# SW.net
KiCad netlist of a schematic drawn in Altium Designer
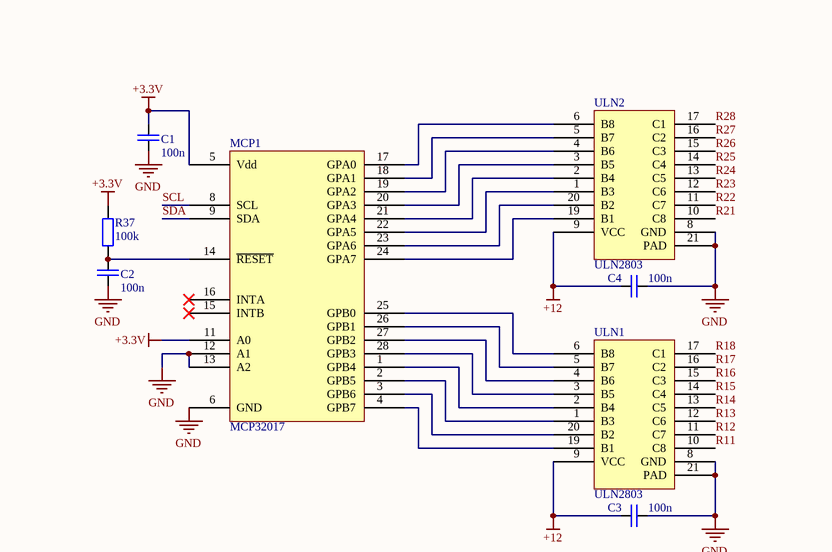
[diagram p0: SW.SchDoc, top left]
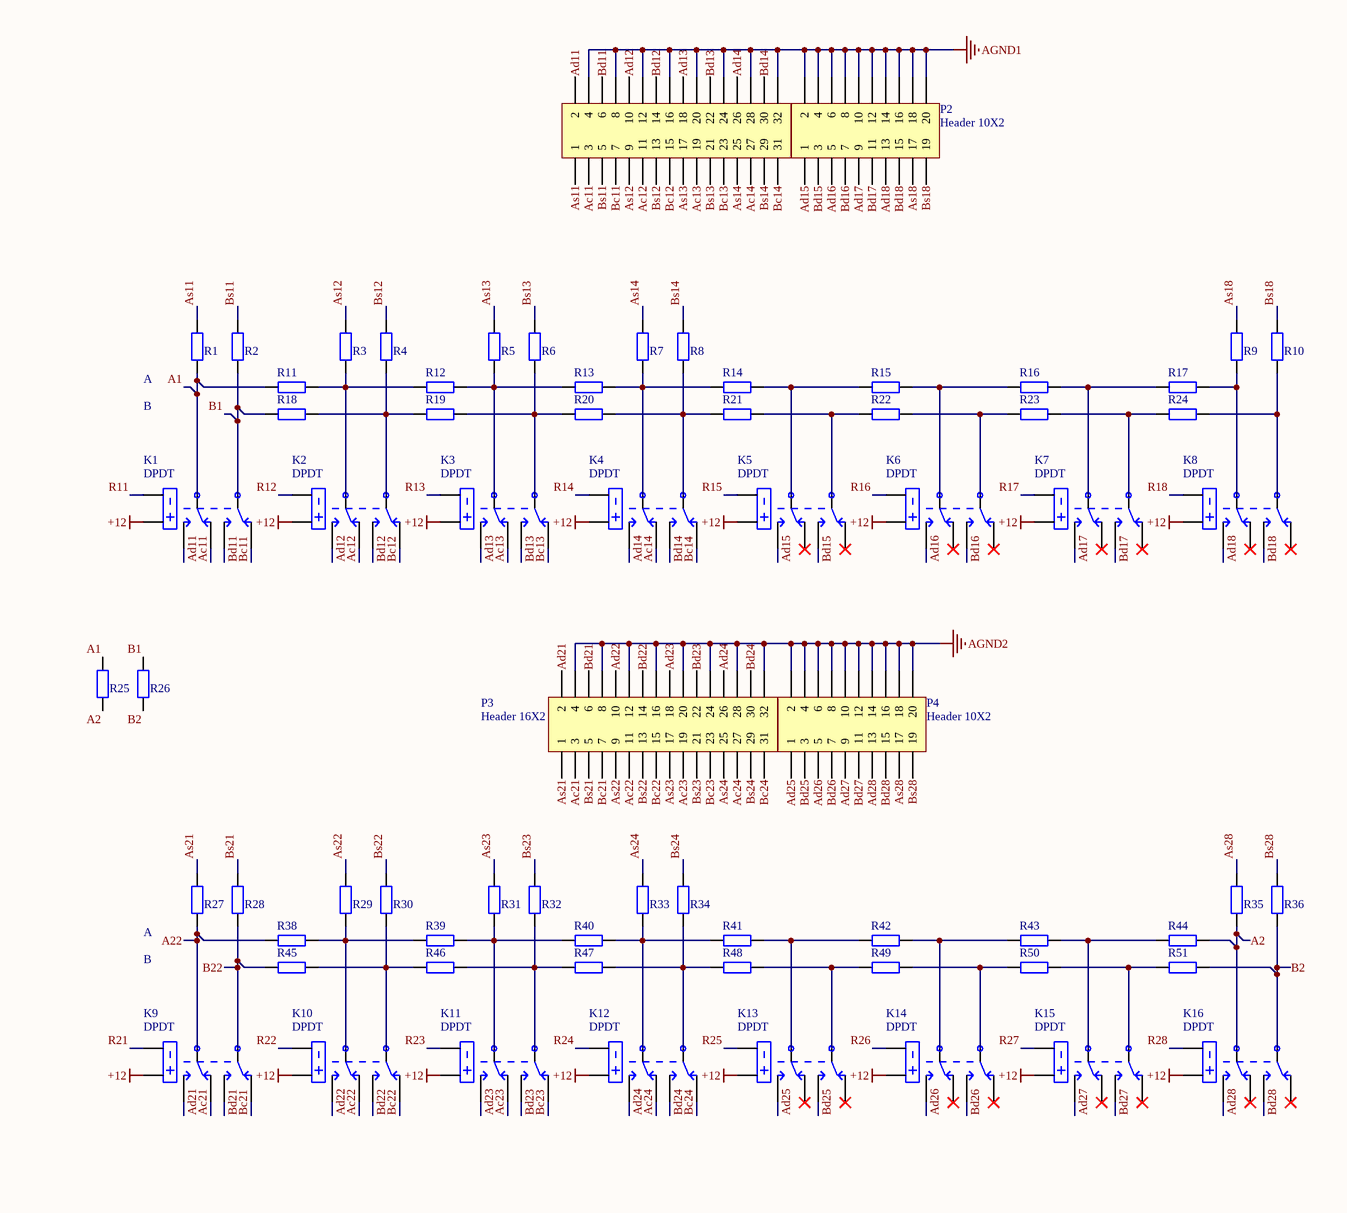
[diagram p1: SW.SchDoc, top right]
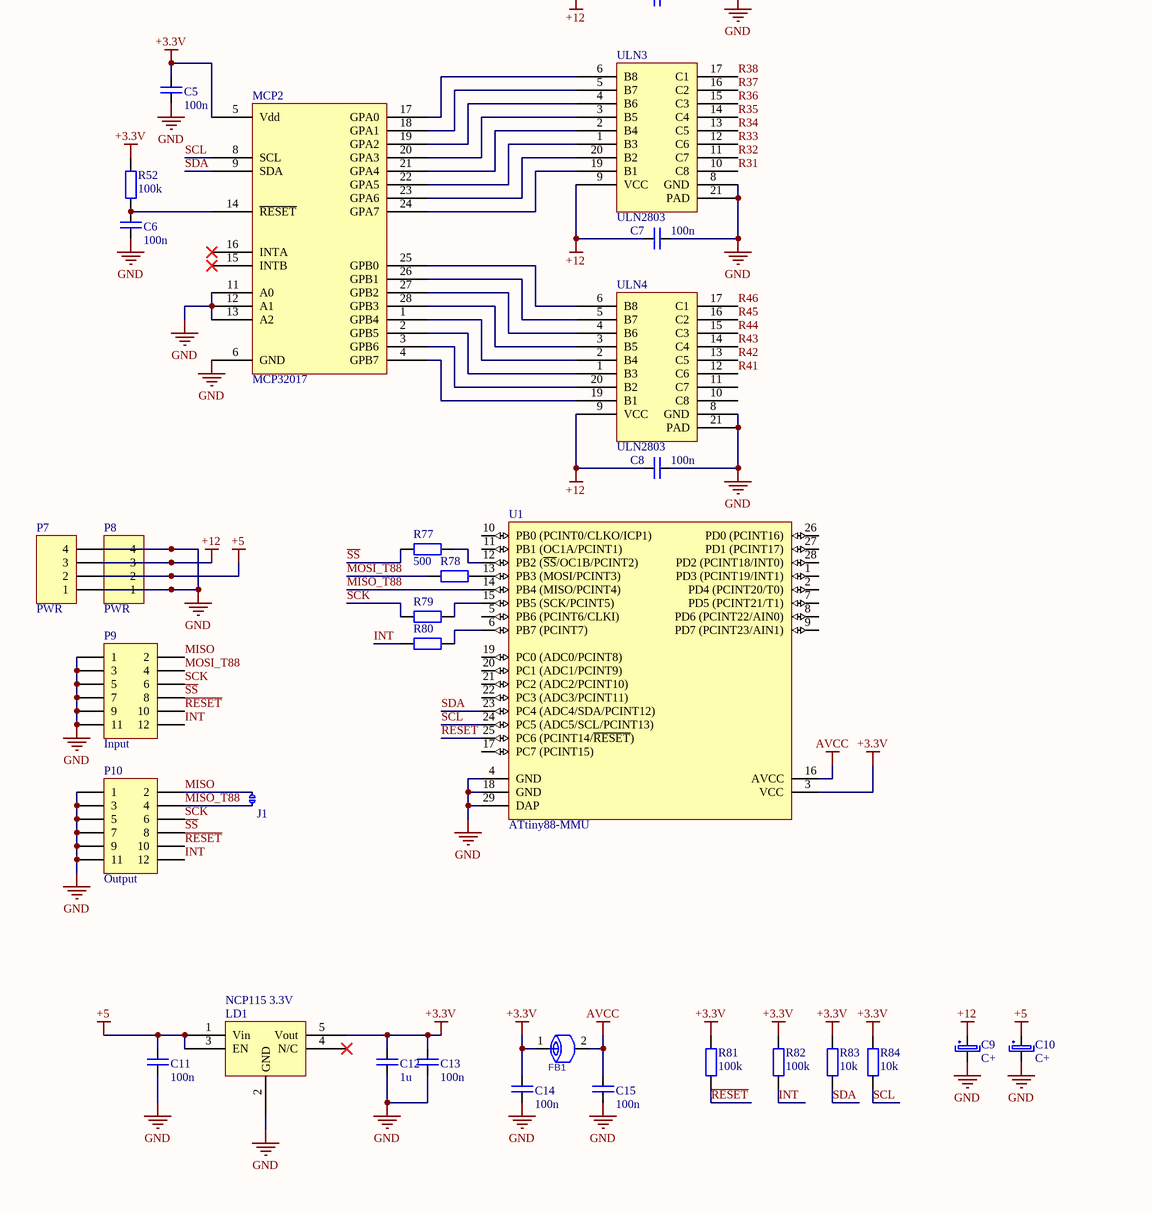
[diagram p2: SW.SchDoc, bottom left]
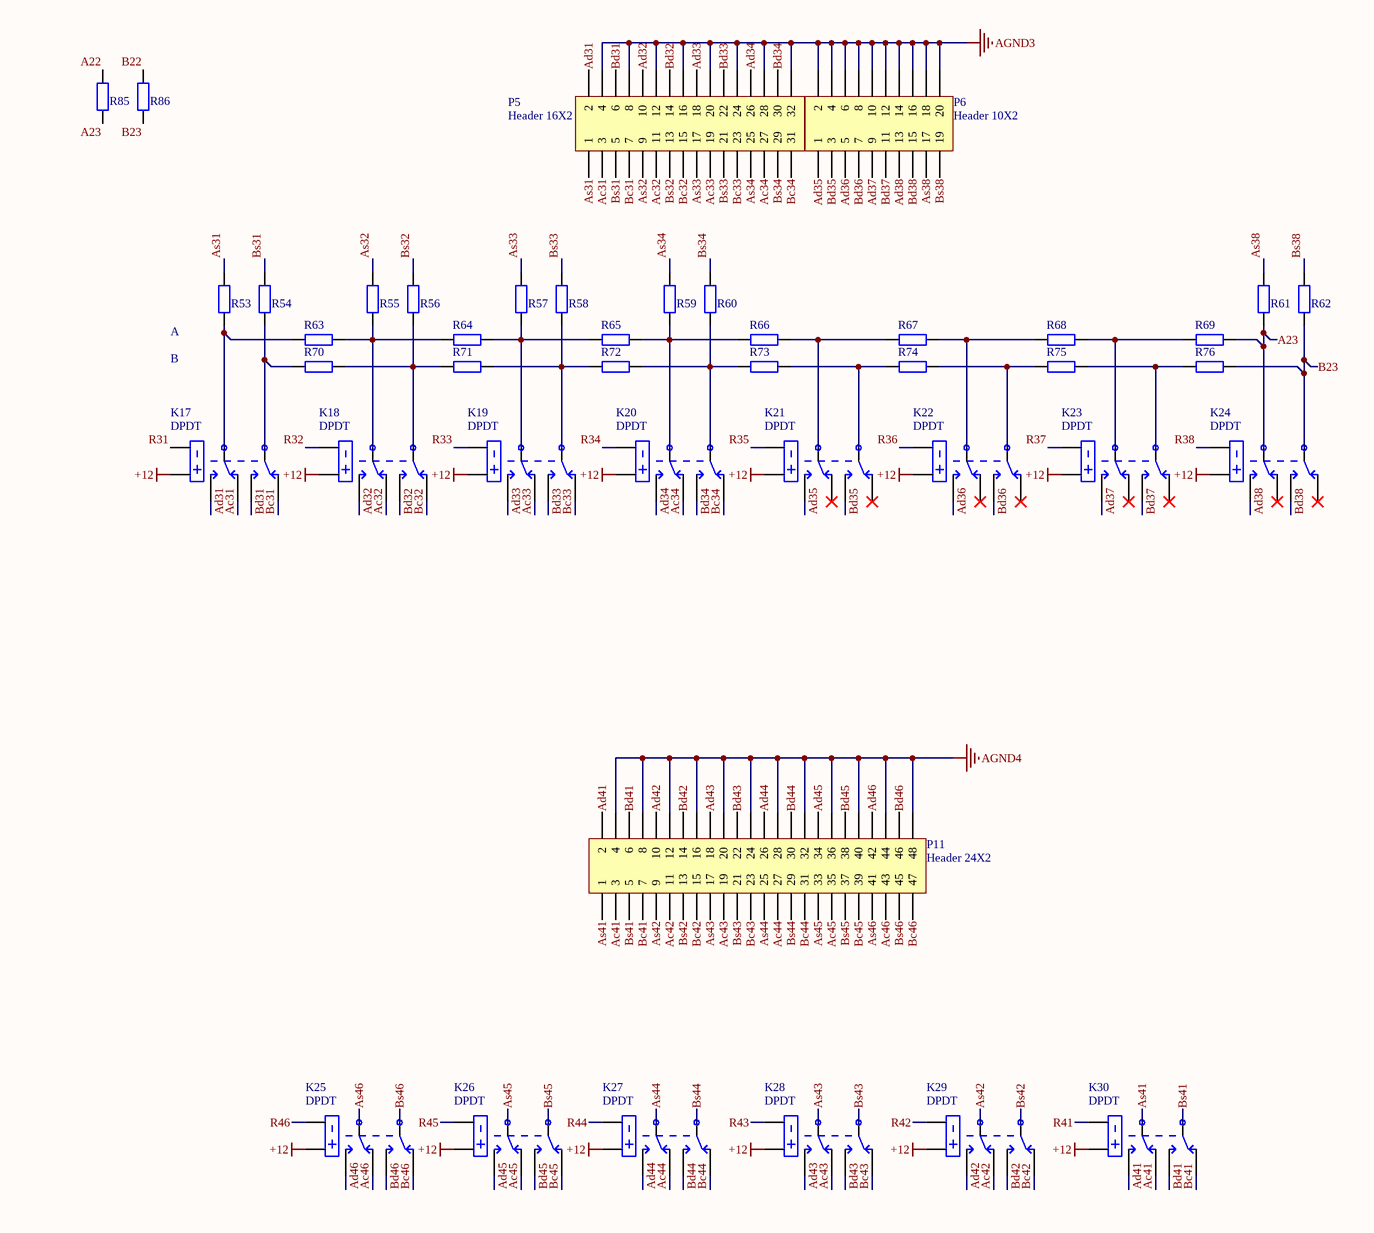
[diagram p3: SW.SchDoc, bottom right]

(export (version "E")
  (design (tool "Eeschema 10.0.6"))
  (components
    (comp (ref "C1")
      (value "100n")
      (footprint "R1005_0402i_L")
      (description "Capacitor")
      (libsource (lib "General") (part "C"))
    )
    (comp (ref "C2")
      (value "100n")
      (footprint "R1005_0402i_L")
      (description "Capacitor")
      (libsource (lib "General") (part "C"))
    )
    (comp (ref "C3")
      (value "100n")
      (footprint "R1005_0402i_L")
      (description "Capacitor")
      (libsource (lib "General") (part "C"))
    )
    (comp (ref "C4")
      (value "100n")
      (footprint "R1005_0402i_L")
      (description "Capacitor")
      (libsource (lib "General") (part "C"))
    )
    (comp (ref "C5")
      (value "100n")
      (footprint "R1005_0402i_L")
      (description "Capacitor")
      (libsource (lib "General") (part "C"))
    )
    (comp (ref "C6")
      (value "100n")
      (footprint "R1005_0402i_L")
      (description "Capacitor")
      (libsource (lib "General") (part "C"))
    )
    (comp (ref "C7")
      (value "100n")
      (footprint "R1005_0402i_L")
      (description "Capacitor")
      (libsource (lib "General") (part "C"))
    )
    (comp (ref "C8")
      (value "100n")
      (footprint "R1005_0402i_L")
      (description "Capacitor")
      (libsource (lib "General") (part "C"))
    )
    (comp (ref "C9")
      (value "C+")
      (footprint "C AlElko 5x11 R2")
      (description "Capacitor Polarized")
      (libsource (lib "General") (part "C+"))
    )
    (comp (ref "C10")
      (value "C+")
      (footprint "C AlElko 5x11 R2")
      (description "Capacitor Polarized")
      (libsource (lib "General") (part "C+"))
    )
    (comp (ref "C11")
      (value "100n")
      (footprint "R1005_0402i_L")
      (description "Capacitor")
      (libsource (lib "General") (part "C"))
    )
    (comp (ref "C12")
      (value "1u")
      (footprint "C1608_0603I_L")
      (description "Capacitor")
      (libsource (lib "General") (part "C"))
    )
    (comp (ref "C13")
      (value "100n")
      (footprint "R1005_0402i_L")
      (description "Capacitor")
      (libsource (lib "General") (part "C"))
    )
    (comp (ref "C14")
      (value "100n")
      (footprint "R1005_0402i_L")
      (description "Capacitor")
      (libsource (lib "General") (part "C"))
    )
    (comp (ref "C15")
      (value "100n")
      (footprint "R1005_0402i_L")
      (description "Capacitor")
      (libsource (lib "General") (part "C"))
    )
    (comp (ref "FB1")
      (value "FERITTE BEAD")
      (footprint "R1608_0603I_L")
      (libsource (lib "General") (part "FERITTE BEAD"))
    )
    (comp (ref "J1")
      (value "Terminator")
      (footprint "solderJumper")
      (libsource (lib "Kon_Tipk") (part "JMP_mini"))
    )
    (comp (ref "K1")
      (value "DPDT")
      (footprint "AXICOM IM-G Relay")
      (description "TE CONNECTIVITY  IM-GR  RELAY, DPDT, NO")
      (libsource (lib "DistopikAltiumLibrary") (part "IM-GR Relay DPDT"))
    )
    (comp (ref "K2")
      (value "DPDT")
      (footprint "AXICOM IM-G Relay")
      (description "TE CONNECTIVITY  IM-GR  RELAY, DPDT, NO")
      (libsource (lib "DistopikAltiumLibrary") (part "IM-GR Relay DPDT"))
    )
    (comp (ref "K3")
      (value "DPDT")
      (footprint "AXICOM IM-G Relay")
      (description "TE CONNECTIVITY  IM-GR  RELAY, DPDT, NO")
      (libsource (lib "DistopikAltiumLibrary") (part "IM-GR Relay DPDT"))
    )
    (comp (ref "K4")
      (value "DPDT")
      (footprint "AXICOM IM-G Relay")
      (description "TE CONNECTIVITY  IM-GR  RELAY, DPDT, NO")
      (libsource (lib "DistopikAltiumLibrary") (part "IM-GR Relay DPDT"))
    )
    (comp (ref "K5")
      (value "DPDT")
      (footprint "AXICOM IM-G Relay")
      (description "TE CONNECTIVITY  IM-GR  RELAY, DPDT, NO")
      (libsource (lib "DistopikAltiumLibrary") (part "IM-GR Relay DPDT"))
    )
    (comp (ref "K6")
      (value "DPDT")
      (footprint "AXICOM IM-G Relay")
      (description "TE CONNECTIVITY  IM-GR  RELAY, DPDT, NO")
      (libsource (lib "DistopikAltiumLibrary") (part "IM-GR Relay DPDT"))
    )
    (comp (ref "K7")
      (value "DPDT")
      (footprint "AXICOM IM-G Relay")
      (description "TE CONNECTIVITY  IM-GR  RELAY, DPDT, NO")
      (libsource (lib "DistopikAltiumLibrary") (part "IM-GR Relay DPDT"))
    )
    (comp (ref "K8")
      (value "DPDT")
      (footprint "AXICOM IM-G Relay")
      (description "TE CONNECTIVITY  IM-GR  RELAY, DPDT, NO")
      (libsource (lib "DistopikAltiumLibrary") (part "IM-GR Relay DPDT"))
    )
    (comp (ref "K9")
      (value "DPDT")
      (footprint "AXICOM IM-G Relay")
      (description "TE CONNECTIVITY  IM-GR  RELAY, DPDT, NO")
      (libsource (lib "DistopikAltiumLibrary") (part "IM-GR Relay DPDT"))
    )
    (comp (ref "K10")
      (value "DPDT")
      (footprint "AXICOM IM-G Relay")
      (description "TE CONNECTIVITY  IM-GR  RELAY, DPDT, NO")
      (libsource (lib "DistopikAltiumLibrary") (part "IM-GR Relay DPDT"))
    )
    (comp (ref "K11")
      (value "DPDT")
      (footprint "AXICOM IM-G Relay")
      (description "TE CONNECTIVITY  IM-GR  RELAY, DPDT, NO")
      (libsource (lib "DistopikAltiumLibrary") (part "IM-GR Relay DPDT"))
    )
    (comp (ref "K12")
      (value "DPDT")
      (footprint "AXICOM IM-G Relay")
      (description "TE CONNECTIVITY  IM-GR  RELAY, DPDT, NO")
      (libsource (lib "DistopikAltiumLibrary") (part "IM-GR Relay DPDT"))
    )
    (comp (ref "K13")
      (value "DPDT")
      (footprint "AXICOM IM-G Relay")
      (description "TE CONNECTIVITY  IM-GR  RELAY, DPDT, NO")
      (libsource (lib "DistopikAltiumLibrary") (part "IM-GR Relay DPDT"))
    )
    (comp (ref "K14")
      (value "DPDT")
      (footprint "AXICOM IM-G Relay")
      (description "TE CONNECTIVITY  IM-GR  RELAY, DPDT, NO")
      (libsource (lib "DistopikAltiumLibrary") (part "IM-GR Relay DPDT"))
    )
    (comp (ref "K15")
      (value "DPDT")
      (footprint "AXICOM IM-G Relay")
      (description "TE CONNECTIVITY  IM-GR  RELAY, DPDT, NO")
      (libsource (lib "DistopikAltiumLibrary") (part "IM-GR Relay DPDT"))
    )
    (comp (ref "K16")
      (value "DPDT")
      (footprint "AXICOM IM-G Relay")
      (description "TE CONNECTIVITY  IM-GR  RELAY, DPDT, NO")
      (libsource (lib "DistopikAltiumLibrary") (part "IM-GR Relay DPDT"))
    )
    (comp (ref "K17")
      (value "DPDT")
      (footprint "AXICOM IM-G Relay")
      (description "TE CONNECTIVITY  IM-GR  RELAY, DPDT, NO")
      (libsource (lib "DistopikAltiumLibrary") (part "IM-GR Relay DPDT"))
    )
    (comp (ref "K18")
      (value "DPDT")
      (footprint "AXICOM IM-G Relay")
      (description "TE CONNECTIVITY  IM-GR  RELAY, DPDT, NO")
      (libsource (lib "DistopikAltiumLibrary") (part "IM-GR Relay DPDT"))
    )
    (comp (ref "K19")
      (value "DPDT")
      (footprint "AXICOM IM-G Relay")
      (description "TE CONNECTIVITY  IM-GR  RELAY, DPDT, NO")
      (libsource (lib "DistopikAltiumLibrary") (part "IM-GR Relay DPDT"))
    )
    (comp (ref "K20")
      (value "DPDT")
      (footprint "AXICOM IM-G Relay")
      (description "TE CONNECTIVITY  IM-GR  RELAY, DPDT, NO")
      (libsource (lib "DistopikAltiumLibrary") (part "IM-GR Relay DPDT"))
    )
    (comp (ref "K21")
      (value "DPDT")
      (footprint "AXICOM IM-G Relay")
      (description "TE CONNECTIVITY  IM-GR  RELAY, DPDT, NO")
      (libsource (lib "DistopikAltiumLibrary") (part "IM-GR Relay DPDT"))
    )
    (comp (ref "K22")
      (value "DPDT")
      (footprint "AXICOM IM-G Relay")
      (description "TE CONNECTIVITY  IM-GR  RELAY, DPDT, NO")
      (libsource (lib "DistopikAltiumLibrary") (part "IM-GR Relay DPDT"))
    )
    (comp (ref "K23")
      (value "DPDT")
      (footprint "AXICOM IM-G Relay")
      (description "TE CONNECTIVITY  IM-GR  RELAY, DPDT, NO")
      (libsource (lib "DistopikAltiumLibrary") (part "IM-GR Relay DPDT"))
    )
    (comp (ref "K24")
      (value "DPDT")
      (footprint "AXICOM IM-G Relay")
      (description "TE CONNECTIVITY  IM-GR  RELAY, DPDT, NO")
      (libsource (lib "DistopikAltiumLibrary") (part "IM-GR Relay DPDT"))
    )
    (comp (ref "K25")
      (value "DPDT")
      (footprint "AXICOM IM-G Relay")
      (description "TE CONNECTIVITY  IM-GR  RELAY, DPDT, NO")
      (libsource (lib "DistopikAltiumLibrary") (part "IM-GR Relay DPDT"))
    )
    (comp (ref "K26")
      (value "DPDT")
      (footprint "AXICOM IM-G Relay")
      (description "TE CONNECTIVITY  IM-GR  RELAY, DPDT, NO")
      (libsource (lib "DistopikAltiumLibrary") (part "IM-GR Relay DPDT"))
    )
    (comp (ref "K27")
      (value "DPDT")
      (footprint "AXICOM IM-G Relay")
      (description "TE CONNECTIVITY  IM-GR  RELAY, DPDT, NO")
      (libsource (lib "DistopikAltiumLibrary") (part "IM-GR Relay DPDT"))
    )
    (comp (ref "K28")
      (value "DPDT")
      (footprint "AXICOM IM-G Relay")
      (description "TE CONNECTIVITY  IM-GR  RELAY, DPDT, NO")
      (libsource (lib "DistopikAltiumLibrary") (part "IM-GR Relay DPDT"))
    )
    (comp (ref "K29")
      (value "DPDT")
      (footprint "AXICOM IM-G Relay")
      (description "TE CONNECTIVITY  IM-GR  RELAY, DPDT, NO")
      (libsource (lib "DistopikAltiumLibrary") (part "IM-GR Relay DPDT"))
    )
    (comp (ref "K30")
      (value "DPDT")
      (footprint "AXICOM IM-G Relay")
      (description "TE CONNECTIVITY  IM-GR  RELAY, DPDT, NO")
      (libsource (lib "DistopikAltiumLibrary") (part "IM-GR Relay DPDT"))
    )
    (comp (ref "LD1")
      (value "NCP115 3.3V")
      (footprint "TSOP95P280X110-6L")
      (libsource (lib "led_ring") (part "NCP115 3.3V"))
    )
    (comp (ref "MCP1")
      (value "MCP32017")
      (footprint "MCP23017 QFN")
      (libsource (lib "Schlib1") (part "MCP32017"))
    )
    (comp (ref "MCP2")
      (value "MCP32017")
      (footprint "MCP23017 QFN")
      (libsource (lib "Schlib1") (part "MCP32017"))
    )
    (comp (ref "P1")
      (value "Header 16X2")
      (footprint "HDR2X16")
      (description "Header, 16-Pin, Dual row")
      (fields (field (name "PUBLISHER") "Altium Limited"))
      (libsource (lib "Miscellaneous Connectors") (part "Header 16X2"))
    )
    (comp (ref "P2")
      (value "Header 10X2")
      (footprint "HDR2X10")
      (description "Header, 10-Pin, Dual row")
      (fields (field (name "PUBLISHER") "Altium Limited"))
      (libsource (lib "Miscellaneous Connectors") (part "Header 10X2"))
    )
    (comp (ref "P3")
      (value "Header 16X2")
      (footprint "HDR2X16")
      (description "Header, 16-Pin, Dual row")
      (fields (field (name "PUBLISHER") "Altium Limited"))
      (libsource (lib "Miscellaneous Connectors") (part "Header 16X2"))
    )
    (comp (ref "P4")
      (value "Header 10X2")
      (footprint "HDR2X10")
      (description "Header, 10-Pin, Dual row")
      (fields (field (name "PUBLISHER") "Altium Limited"))
      (libsource (lib "Miscellaneous Connectors") (part "Header 10X2"))
    )
    (comp (ref "P5")
      (value "Header 16X2")
      (footprint "HDR2X16")
      (description "Header, 16-Pin, Dual row")
      (fields (field (name "PUBLISHER") "Altium Limited"))
      (libsource (lib "Miscellaneous Connectors") (part "Header 16X2"))
    )
    (comp (ref "P6")
      (value "Header 10X2")
      (footprint "HDR2X10")
      (description "Header, 10-Pin, Dual row")
      (fields (field (name "PUBLISHER") "Altium Limited"))
      (libsource (lib "Miscellaneous Connectors") (part "Header 10X2"))
    )
    (comp (ref "P7")
      (value "PWR")
      (footprint "HDR1X4")
      (description "Header, 4-Pin")
      (fields (field (name "PUBLISHER") "Altium Limited"))
      (libsource (lib "Miscellaneous Connectors") (part "Header 4"))
    )
    (comp (ref "P8")
      (value "PWR")
      (footprint "HDR1X4")
      (description "Header, 4-Pin")
      (fields (field (name "PUBLISHER") "Altium Limited"))
      (libsource (lib "Miscellaneous Connectors") (part "Header 4"))
    )
    (comp (ref "P9")
      (value "Input")
      (footprint "1.27mm SMD conn")
      (description "Header, 6-Pin, Dual row")
      (fields (field (name "PUBLISHER") "Altium Limited"))
      (libsource (lib "Miscellaneous Connectors") (part "Header 6X2"))
    )
    (comp (ref "P10")
      (value "Output")
      (footprint "1.27mm SMD conn")
      (description "Header, 6-Pin, Dual row")
      (fields (field (name "PUBLISHER") "Altium Limited"))
      (libsource (lib "Miscellaneous Connectors") (part "Header 6X2"))
    )
    (comp (ref "P11")
      (value "Header 24X2")
      (footprint "HDR2X24")
      (description "Header, 24-Pin, Dual row")
      (fields (field (name "PUBLISHER") "Altium Limited"))
      (libsource (lib "Miscellaneous Connectors") (part "Header 24X2"))
    )
    (comp (ref "R1") (value "R") (footprint "R1608_0603I_L") (libsource (lib "General") (part "R")))
    (comp (ref "R2") (value "R") (footprint "R1608_0603I_L") (libsource (lib "General") (part "R")))
    (comp (ref "R3") (value "R") (footprint "R1608_0603I_L") (libsource (lib "General") (part "R")))
    (comp (ref "R4") (value "R") (footprint "R1608_0603I_L") (libsource (lib "General") (part "R")))
    (comp (ref "R5") (value "R") (footprint "R1608_0603I_L") (libsource (lib "General") (part "R")))
    (comp (ref "R6") (value "R") (footprint "R1608_0603I_L") (libsource (lib "General") (part "R")))
    (comp (ref "R7") (value "R") (footprint "R1608_0603I_L") (libsource (lib "General") (part "R")))
    (comp (ref "R8") (value "R") (footprint "R1608_0603I_L") (libsource (lib "General") (part "R")))
    (comp (ref "R9") (value "R") (footprint "R1608_0603I_L") (libsource (lib "General") (part "R")))
    (comp (ref "R10") (value "R") (footprint "R1608_0603I_L") (libsource (lib "General") (part "R")))
    (comp (ref "R11") (value "R") (footprint "R1608_0603I_L") (libsource (lib "General") (part "R")))
    (comp (ref "R12") (value "R") (footprint "R1608_0603I_L") (libsource (lib "General") (part "R")))
    (comp (ref "R13") (value "R") (footprint "R1608_0603I_L") (libsource (lib "General") (part "R")))
    (comp (ref "R14") (value "R") (footprint "R1608_0603I_L") (libsource (lib "General") (part "R")))
    (comp (ref "R15") (value "R") (footprint "R1608_0603I_L") (libsource (lib "General") (part "R")))
    (comp (ref "R16") (value "R") (footprint "R1608_0603I_L") (libsource (lib "General") (part "R")))
    (comp (ref "R17") (value "R") (footprint "R1608_0603I_L") (libsource (lib "General") (part "R")))
    (comp (ref "R18") (value "R") (footprint "R1608_0603I_L") (libsource (lib "General") (part "R")))
    (comp (ref "R19") (value "R") (footprint "R1608_0603I_L") (libsource (lib "General") (part "R")))
    (comp (ref "R20") (value "R") (footprint "R1608_0603I_L") (libsource (lib "General") (part "R")))
    (comp (ref "R21") (value "R") (footprint "R1608_0603I_L") (libsource (lib "General") (part "R")))
    (comp (ref "R22") (value "R") (footprint "R1608_0603I_L") (libsource (lib "General") (part "R")))
    (comp (ref "R23") (value "R") (footprint "R1608_0603I_L") (libsource (lib "General") (part "R")))
    (comp (ref "R24") (value "R") (footprint "R1608_0603I_L") (libsource (lib "General") (part "R")))
    (comp (ref "R25") (value "R") (footprint "R1608_0603I_L") (libsource (lib "General") (part "R")))
    (comp (ref "R26") (value "R") (footprint "R1608_0603I_L") (libsource (lib "General") (part "R")))
    (comp (ref "R27") (value "R") (footprint "R1608_0603I_L") (libsource (lib "General") (part "R")))
    (comp (ref "R28") (value "R") (footprint "R1608_0603I_L") (libsource (lib "General") (part "R")))
    (comp (ref "R29") (value "R") (footprint "R1608_0603I_L") (libsource (lib "General") (part "R")))
    (comp (ref "R30") (value "R") (footprint "R1608_0603I_L") (libsource (lib "General") (part "R")))
    (comp (ref "R31") (value "R") (footprint "R1608_0603I_L") (libsource (lib "General") (part "R")))
    (comp (ref "R32") (value "R") (footprint "R1608_0603I_L") (libsource (lib "General") (part "R")))
    (comp (ref "R33") (value "R") (footprint "R1608_0603I_L") (libsource (lib "General") (part "R")))
    (comp (ref "R34") (value "R") (footprint "R1608_0603I_L") (libsource (lib "General") (part "R")))
    (comp (ref "R35") (value "R") (footprint "R1608_0603I_L") (libsource (lib "General") (part "R")))
    (comp (ref "R36") (value "R") (footprint "R1608_0603I_L") (libsource (lib "General") (part "R")))
    (comp (ref "R37")
      (value "100k")
      (footprint "R1005_0402i_L")
      (description "R")
      (libsource (lib "General") (part "R"))
    )
    (comp (ref "R38") (value "R") (footprint "R1608_0603I_L") (libsource (lib "General") (part "R")))
    (comp (ref "R39") (value "R") (footprint "R1608_0603I_L") (libsource (lib "General") (part "R")))
    (comp (ref "R40") (value "R") (footprint "R1608_0603I_L") (libsource (lib "General") (part "R")))
    (comp (ref "R41") (value "R") (footprint "R1608_0603I_L") (libsource (lib "General") (part "R")))
    (comp (ref "R42") (value "R") (footprint "R1608_0603I_L") (libsource (lib "General") (part "R")))
    (comp (ref "R43") (value "R") (footprint "R1608_0603I_L") (libsource (lib "General") (part "R")))
    (comp (ref "R44") (value "R") (footprint "R1608_0603I_L") (libsource (lib "General") (part "R")))
    (comp (ref "R45") (value "R") (footprint "R1608_0603I_L") (libsource (lib "General") (part "R")))
    (comp (ref "R46") (value "R") (footprint "R1608_0603I_L") (libsource (lib "General") (part "R")))
    (comp (ref "R47") (value "R") (footprint "R1608_0603I_L") (libsource (lib "General") (part "R")))
    (comp (ref "R48") (value "R") (footprint "R1608_0603I_L") (libsource (lib "General") (part "R")))
    (comp (ref "R49") (value "R") (footprint "R1608_0603I_L") (libsource (lib "General") (part "R")))
    (comp (ref "R50") (value "R") (footprint "R1608_0603I_L") (libsource (lib "General") (part "R")))
    (comp (ref "R51") (value "R") (footprint "R1608_0603I_L") (libsource (lib "General") (part "R")))
    (comp (ref "R52")
      (value "100k")
      (footprint "R1005_0402i_L")
      (description "R")
      (libsource (lib "General") (part "R"))
    )
    (comp (ref "R53") (value "R") (footprint "R1608_0603I_L") (libsource (lib "General") (part "R")))
    (comp (ref "R54") (value "R") (footprint "R1608_0603I_L") (libsource (lib "General") (part "R")))
    (comp (ref "R55") (value "R") (footprint "R1608_0603I_L") (libsource (lib "General") (part "R")))
    (comp (ref "R56") (value "R") (footprint "R1608_0603I_L") (libsource (lib "General") (part "R")))
    (comp (ref "R57") (value "R") (footprint "R1608_0603I_L") (libsource (lib "General") (part "R")))
    (comp (ref "R58") (value "R") (footprint "R1608_0603I_L") (libsource (lib "General") (part "R")))
    (comp (ref "R59") (value "R") (footprint "R1608_0603I_L") (libsource (lib "General") (part "R")))
    (comp (ref "R60") (value "R") (footprint "R1608_0603I_L") (libsource (lib "General") (part "R")))
    (comp (ref "R61") (value "R") (footprint "R1608_0603I_L") (libsource (lib "General") (part "R")))
    (comp (ref "R62") (value "R") (footprint "R1608_0603I_L") (libsource (lib "General") (part "R")))
    (comp (ref "R63") (value "R") (footprint "R1608_0603I_L") (libsource (lib "General") (part "R")))
    (comp (ref "R64") (value "R") (footprint "R1608_0603I_L") (libsource (lib "General") (part "R")))
    (comp (ref "R65") (value "R") (footprint "R1608_0603I_L") (libsource (lib "General") (part "R")))
    (comp (ref "R66") (value "R") (footprint "R1608_0603I_L") (libsource (lib "General") (part "R")))
    (comp (ref "R67") (value "R") (footprint "R1608_0603I_L") (libsource (lib "General") (part "R")))
    (comp (ref "R68") (value "R") (footprint "R1608_0603I_L") (libsource (lib "General") (part "R")))
    (comp (ref "R69") (value "R") (footprint "R1608_0603I_L") (libsource (lib "General") (part "R")))
    (comp (ref "R70") (value "R") (footprint "R1608_0603I_L") (libsource (lib "General") (part "R")))
    (comp (ref "R71") (value "R") (footprint "R1608_0603I_L") (libsource (lib "General") (part "R")))
    (comp (ref "R72") (value "R") (footprint "R1608_0603I_L") (libsource (lib "General") (part "R")))
    (comp (ref "R73") (value "R") (footprint "R1608_0603I_L") (libsource (lib "General") (part "R")))
    (comp (ref "R74") (value "R") (footprint "R1608_0603I_L") (libsource (lib "General") (part "R")))
    (comp (ref "R75") (value "R") (footprint "R1608_0603I_L") (libsource (lib "General") (part "R")))
    (comp (ref "R76") (value "R") (footprint "R1608_0603I_L") (libsource (lib "General") (part "R")))
    (comp (ref "R77")
      (value "500")
      (footprint "R1005_0402i_L")
      (description "R")
      (libsource (lib "General") (part "R"))
    )
    (comp (ref "R78")
      (value "500")
      (footprint "R1005_0402i_L")
      (description "R")
      (libsource (lib "General") (part "R"))
    )
    (comp (ref "R79")
      (value "500")
      (footprint "R1005_0402i_L")
      (description "R")
      (libsource (lib "General") (part "R"))
    )
    (comp (ref "R80")
      (value "500")
      (footprint "R1005_0402i_L")
      (description "R")
      (libsource (lib "General") (part "R"))
    )
    (comp (ref "R81")
      (value "100k")
      (footprint "R1005_0402i_L")
      (description "R")
      (libsource (lib "General") (part "R"))
    )
    (comp (ref "R82")
      (value "100k")
      (footprint "R1005_0402i_L")
      (description "R")
      (libsource (lib "General") (part "R"))
    )
    (comp (ref "R83")
      (value "10k")
      (footprint "R1005_0402i_L")
      (description "R")
      (libsource (lib "General") (part "R"))
    )
    (comp (ref "R84")
      (value "10k")
      (footprint "R1005_0402i_L")
      (description "R")
      (libsource (lib "General") (part "R"))
    )
    (comp (ref "R85") (value "R") (footprint "R1608_0603I_L") (libsource (lib "General") (part "R")))
    (comp (ref "R86") (value "R") (footprint "R1608_0603I_L") (libsource (lib "General") (part "R")))
    (comp (ref "U1")
      (value "ATtiny88-MMU")
      (footprint "28M1_N")
      (fields (field (name "PUBLISHER") "Altium Limited"))
      (libsource (lib "Encoder_w_LED_ring") (part "ATtiny88-MMU"))
    )
    (comp (ref "ULN1")
      (value "ULN2803")
      (footprint "QFN127P600-8N")
      (libsource (lib "Schlib1") (part "ULN2803"))
    )
    (comp (ref "ULN2")
      (value "ULN2803")
      (footprint "QFN127P600-8N")
      (libsource (lib "Schlib1") (part "ULN2803"))
    )
    (comp (ref "ULN3")
      (value "ULN2803")
      (footprint "QFN127P600-8N")
      (libsource (lib "Schlib1") (part "ULN2803"))
    )
    (comp (ref "ULN4")
      (value "ULN2803")
      (footprint "QFN127P600-8N")
      (libsource (lib "Schlib1") (part "ULN2803"))
    )
  )
  (nets
    (net (code "1") (name "+3.3V") (class "Default")
      (node (ref "C1") (pin "2") (pinfunction "2_2") (pintype "passive"))
      (node (ref "C12") (pin "1") (pinfunction "1_1") (pintype "passive"))
      (node (ref "C13") (pin "1") (pinfunction "1_1") (pintype "passive"))
      (node (ref "C14") (pin "1") (pinfunction "1_1") (pintype "passive"))
      (node (ref "C5") (pin "2") (pinfunction "2_2") (pintype "passive"))
      (node (ref "FB1") (pin "1") (pintype "passive"))
      (node (ref "LD1") (pin "5") (pinfunction "Vout_5") (pintype "passive"))
      (node (ref "MCP1") (pin "11") (pinfunction "A0_11") (pintype "passive"))
      (node (ref "MCP1") (pin "5") (pinfunction "Vdd_5") (pintype "passive"))
      (node (ref "MCP2") (pin "5") (pinfunction "Vdd_5") (pintype "passive"))
      (node (ref "R37") (pin "1") (pintype "passive"))
      (node (ref "R52") (pin "1") (pintype "passive"))
      (node (ref "R81") (pin "1") (pintype "passive"))
      (node (ref "R82") (pin "1") (pintype "passive"))
      (node (ref "R83") (pin "1") (pintype "passive"))
      (node (ref "R84") (pin "1") (pintype "passive"))
      (node (ref "U1") (pin "3") (pinfunction "VCC_3") (pintype "power_in"))
    )
    (net (code "2") (name "+5") (class "Default")
      (node (ref "C10") (pin "1") (pinfunction "1_1") (pintype "passive"))
      (node (ref "C11") (pin "1") (pinfunction "1_1") (pintype "passive"))
      (node (ref "LD1") (pin "1") (pinfunction "Vin_1") (pintype "passive"))
      (node (ref "LD1") (pin "3") (pinfunction "EN_3") (pintype "passive"))
      (node (ref "P7") (pin "2") (pinfunction "2_2") (pintype "passive"))
      (node (ref "P8") (pin "2") (pinfunction "2_2") (pintype "passive"))
    )
    (net (code "3") (name "+12") (class "Default")
      (node (ref "C3") (pin "1") (pinfunction "1_1") (pintype "passive"))
      (node (ref "C4") (pin "1") (pinfunction "1_1") (pintype "passive"))
      (node (ref "C7") (pin "1") (pinfunction "1_1") (pintype "passive"))
      (node (ref "C8") (pin "1") (pinfunction "1_1") (pintype "passive"))
      (node (ref "C9") (pin "1") (pinfunction "1_1") (pintype "passive"))
      (node (ref "K1") (pin "1") (pinfunction "1_1") (pintype "passive"))
      (node (ref "K10") (pin "1") (pinfunction "1_1") (pintype "passive"))
      (node (ref "K11") (pin "1") (pinfunction "1_1") (pintype "passive"))
      (node (ref "K12") (pin "1") (pinfunction "1_1") (pintype "passive"))
      (node (ref "K13") (pin "1") (pinfunction "1_1") (pintype "passive"))
      (node (ref "K14") (pin "1") (pinfunction "1_1") (pintype "passive"))
      (node (ref "K15") (pin "1") (pinfunction "1_1") (pintype "passive"))
      (node (ref "K16") (pin "1") (pinfunction "1_1") (pintype "passive"))
      (node (ref "K17") (pin "1") (pinfunction "1_1") (pintype "passive"))
      (node (ref "K18") (pin "1") (pinfunction "1_1") (pintype "passive"))
      (node (ref "K19") (pin "1") (pinfunction "1_1") (pintype "passive"))
      (node (ref "K2") (pin "1") (pinfunction "1_1") (pintype "passive"))
      (node (ref "K20") (pin "1") (pinfunction "1_1") (pintype "passive"))
      (node (ref "K21") (pin "1") (pinfunction "1_1") (pintype "passive"))
      (node (ref "K22") (pin "1") (pinfunction "1_1") (pintype "passive"))
      (node (ref "K23") (pin "1") (pinfunction "1_1") (pintype "passive"))
      (node (ref "K24") (pin "1") (pinfunction "1_1") (pintype "passive"))
      (node (ref "K25") (pin "1") (pinfunction "1_1") (pintype "passive"))
      (node (ref "K26") (pin "1") (pinfunction "1_1") (pintype "passive"))
      (node (ref "K27") (pin "1") (pinfunction "1_1") (pintype "passive"))
      (node (ref "K28") (pin "1") (pinfunction "1_1") (pintype "passive"))
      (node (ref "K29") (pin "1") (pinfunction "1_1") (pintype "passive"))
      (node (ref "K3") (pin "1") (pinfunction "1_1") (pintype "passive"))
      (node (ref "K30") (pin "1") (pinfunction "1_1") (pintype "passive"))
      (node (ref "K4") (pin "1") (pinfunction "1_1") (pintype "passive"))
      (node (ref "K5") (pin "1") (pinfunction "1_1") (pintype "passive"))
      (node (ref "K6") (pin "1") (pinfunction "1_1") (pintype "passive"))
      (node (ref "K7") (pin "1") (pinfunction "1_1") (pintype "passive"))
      (node (ref "K8") (pin "1") (pinfunction "1_1") (pintype "passive"))
      (node (ref "K9") (pin "1") (pinfunction "1_1") (pintype "passive"))
      (node (ref "P7") (pin "3") (pinfunction "3_3") (pintype "passive"))
      (node (ref "P8") (pin "3") (pinfunction "3_3") (pintype "passive"))
      (node (ref "ULN1") (pin "9") (pinfunction "VCC_9") (pintype "passive"))
      (node (ref "ULN2") (pin "9") (pinfunction "VCC_9") (pintype "passive"))
      (node (ref "ULN3") (pin "9") (pinfunction "VCC_9") (pintype "passive"))
      (node (ref "ULN4") (pin "9") (pinfunction "VCC_9") (pintype "passive"))
    )
    (net (code "4") (name "/A1") (class "Default")
      (node (ref "K1") (pin "3") (pinfunction "3_3") (pintype "passive"))
      (node (ref "R1") (pin "1") (pintype "passive"))
      (node (ref "R11") (pin "1") (pintype "passive"))
      (node (ref "R25") (pin "2") (pintype "passive"))
    )
    (net (code "5") (name "/A2") (class "Default")
      (node (ref "K16") (pin "3") (pinfunction "3_3") (pintype "passive"))
      (node (ref "R25") (pin "1") (pintype "passive"))
      (node (ref "R35") (pin "1") (pintype "passive"))
      (node (ref "R44") (pin "2") (pintype "passive"))
    )
    (net (code "6") (name "/A22") (class "Default")
      (node (ref "K9") (pin "3") (pinfunction "3_3") (pintype "passive"))
      (node (ref "R27") (pin "1") (pintype "passive"))
      (node (ref "R38") (pin "1") (pintype "passive"))
      (node (ref "R85") (pin "2") (pintype "passive"))
    )
    (net (code "7") (name "/A23") (class "Default")
      (node (ref "K24") (pin "3") (pinfunction "3_3") (pintype "passive"))
      (node (ref "R61") (pin "1") (pintype "passive"))
      (node (ref "R69") (pin "2") (pintype "passive"))
      (node (ref "R85") (pin "1") (pintype "passive"))
    )
    (net (code "8") (name "/Ac11") (class "Default")
      (node (ref "K1") (pin "2") (pinfunction "2_2") (pintype "passive"))
      (node (ref "P1") (pin "3") (pinfunction "3_3") (pintype "passive"))
    )
    (net (code "9") (name "/Ac12") (class "Default")
      (node (ref "K2") (pin "2") (pinfunction "2_2") (pintype "passive"))
      (node (ref "P1") (pin "11") (pinfunction "11_11") (pintype "passive"))
    )
    (net (code "10") (name "/Ac13") (class "Default")
      (node (ref "K3") (pin "2") (pinfunction "2_2") (pintype "passive"))
      (node (ref "P1") (pin "19") (pinfunction "19_19") (pintype "passive"))
    )
    (net (code "11") (name "/Ac14") (class "Default")
      (node (ref "K4") (pin "2") (pinfunction "2_2") (pintype "passive"))
      (node (ref "P1") (pin "27") (pinfunction "27_27") (pintype "passive"))
    )
    (net (code "12") (name "/Ac21") (class "Default")
      (node (ref "K9") (pin "2") (pinfunction "2_2") (pintype "passive"))
      (node (ref "P3") (pin "3") (pinfunction "3_3") (pintype "passive"))
    )
    (net (code "13") (name "/Ac22") (class "Default")
      (node (ref "K10") (pin "2") (pinfunction "2_2") (pintype "passive"))
      (node (ref "P3") (pin "11") (pinfunction "11_11") (pintype "passive"))
    )
    (net (code "14") (name "/Ac23") (class "Default")
      (node (ref "K11") (pin "2") (pinfunction "2_2") (pintype "passive"))
      (node (ref "P3") (pin "19") (pinfunction "19_19") (pintype "passive"))
    )
    (net (code "15") (name "/Ac24") (class "Default")
      (node (ref "K12") (pin "2") (pinfunction "2_2") (pintype "passive"))
      (node (ref "P3") (pin "27") (pinfunction "27_27") (pintype "passive"))
    )
    (net (code "16") (name "/Ac31") (class "Default")
      (node (ref "K17") (pin "2") (pinfunction "2_2") (pintype "passive"))
      (node (ref "P5") (pin "3") (pinfunction "3_3") (pintype "passive"))
    )
    (net (code "17") (name "/Ac32") (class "Default")
      (node (ref "K18") (pin "2") (pinfunction "2_2") (pintype "passive"))
      (node (ref "P5") (pin "11") (pinfunction "11_11") (pintype "passive"))
    )
    (net (code "18") (name "/Ac33") (class "Default")
      (node (ref "K19") (pin "2") (pinfunction "2_2") (pintype "passive"))
      (node (ref "P5") (pin "19") (pinfunction "19_19") (pintype "passive"))
    )
    (net (code "19") (name "/Ac34") (class "Default")
      (node (ref "K20") (pin "2") (pinfunction "2_2") (pintype "passive"))
      (node (ref "P5") (pin "27") (pinfunction "27_27") (pintype "passive"))
    )
    (net (code "20") (name "/Ac41") (class "Default")
      (node (ref "K30") (pin "2") (pinfunction "2_2") (pintype "passive"))
      (node (ref "P11") (pin "3") (pinfunction "3_3") (pintype "passive"))
    )
    (net (code "21") (name "/Ac42") (class "Default")
      (node (ref "K29") (pin "2") (pinfunction "2_2") (pintype "passive"))
      (node (ref "P11") (pin "11") (pinfunction "11_11") (pintype "passive"))
    )
    (net (code "22") (name "/Ac43") (class "Default")
      (node (ref "K28") (pin "2") (pinfunction "2_2") (pintype "passive"))
      (node (ref "P11") (pin "19") (pinfunction "19_19") (pintype "passive"))
    )
    (net (code "23") (name "/Ac44") (class "Default")
      (node (ref "K27") (pin "2") (pinfunction "2_2") (pintype "passive"))
      (node (ref "P11") (pin "27") (pinfunction "27_27") (pintype "passive"))
    )
    (net (code "24") (name "/Ac45") (class "Default")
      (node (ref "K26") (pin "2") (pinfunction "2_2") (pintype "passive"))
      (node (ref "P11") (pin "35") (pinfunction "35_35") (pintype "passive"))
    )
    (net (code "25") (name "/Ac46") (class "Default")
      (node (ref "K25") (pin "2") (pinfunction "2_2") (pintype "passive"))
      (node (ref "P11") (pin "43") (pinfunction "43_43") (pintype "passive"))
    )
    (net (code "26") (name "/Ad11") (class "Default")
      (node (ref "K1") (pin "4") (pinfunction "4_4") (pintype "passive"))
      (node (ref "P1") (pin "2") (pinfunction "2_2") (pintype "passive"))
    )
    (net (code "27") (name "/Ad12") (class "Default")
      (node (ref "K2") (pin "4") (pinfunction "4_4") (pintype "passive"))
      (node (ref "P1") (pin "10") (pinfunction "10_10") (pintype "passive"))
    )
    (net (code "28") (name "/Ad13") (class "Default")
      (node (ref "K3") (pin "4") (pinfunction "4_4") (pintype "passive"))
      (node (ref "P1") (pin "18") (pinfunction "18_18") (pintype "passive"))
    )
    (net (code "29") (name "/Ad14") (class "Default")
      (node (ref "K4") (pin "4") (pinfunction "4_4") (pintype "passive"))
      (node (ref "P1") (pin "26") (pinfunction "26_26") (pintype "passive"))
    )
    (net (code "30") (name "/Ad15") (class "Default")
      (node (ref "K5") (pin "4") (pinfunction "4_4") (pintype "passive"))
      (node (ref "P2") (pin "1") (pinfunction "1_1") (pintype "passive"))
    )
    (net (code "31") (name "/Ad16") (class "Default")
      (node (ref "K6") (pin "4") (pinfunction "4_4") (pintype "passive"))
      (node (ref "P2") (pin "5") (pinfunction "5_5") (pintype "passive"))
    )
    (net (code "32") (name "/Ad17") (class "Default")
      (node (ref "K7") (pin "4") (pinfunction "4_4") (pintype "passive"))
      (node (ref "P2") (pin "9") (pinfunction "9_9") (pintype "passive"))
    )
    (net (code "33") (name "/Ad18") (class "Default")
      (node (ref "K8") (pin "4") (pinfunction "4_4") (pintype "passive"))
      (node (ref "P2") (pin "13") (pinfunction "13_13") (pintype "passive"))
    )
    (net (code "34") (name "/Ad21") (class "Default")
      (node (ref "K9") (pin "4") (pinfunction "4_4") (pintype "passive"))
      (node (ref "P3") (pin "2") (pinfunction "2_2") (pintype "passive"))
    )
    (net (code "35") (name "/Ad22") (class "Default")
      (node (ref "K10") (pin "4") (pinfunction "4_4") (pintype "passive"))
      (node (ref "P3") (pin "10") (pinfunction "10_10") (pintype "passive"))
    )
    (net (code "36") (name "/Ad23") (class "Default")
      (node (ref "K11") (pin "4") (pinfunction "4_4") (pintype "passive"))
      (node (ref "P3") (pin "18") (pinfunction "18_18") (pintype "passive"))
    )
    (net (code "37") (name "/Ad24") (class "Default")
      (node (ref "K12") (pin "4") (pinfunction "4_4") (pintype "passive"))
      (node (ref "P3") (pin "26") (pinfunction "26_26") (pintype "passive"))
    )
    (net (code "38") (name "/Ad25") (class "Default")
      (node (ref "K13") (pin "4") (pinfunction "4_4") (pintype "passive"))
      (node (ref "P4") (pin "1") (pinfunction "1_1") (pintype "passive"))
    )
    (net (code "39") (name "/Ad26") (class "Default")
      (node (ref "K14") (pin "4") (pinfunction "4_4") (pintype "passive"))
      (node (ref "P4") (pin "5") (pinfunction "5_5") (pintype "passive"))
    )
    (net (code "40") (name "/Ad27") (class "Default")
      (node (ref "K15") (pin "4") (pinfunction "4_4") (pintype "passive"))
      (node (ref "P4") (pin "9") (pinfunction "9_9") (pintype "passive"))
    )
    (net (code "41") (name "/Ad28") (class "Default")
      (node (ref "K16") (pin "4") (pinfunction "4_4") (pintype "passive"))
      (node (ref "P4") (pin "13") (pinfunction "13_13") (pintype "passive"))
    )
    (net (code "42") (name "/Ad31") (class "Default")
      (node (ref "K17") (pin "4") (pinfunction "4_4") (pintype "passive"))
      (node (ref "P5") (pin "2") (pinfunction "2_2") (pintype "passive"))
    )
    (net (code "43") (name "/Ad32") (class "Default")
      (node (ref "K18") (pin "4") (pinfunction "4_4") (pintype "passive"))
      (node (ref "P5") (pin "10") (pinfunction "10_10") (pintype "passive"))
    )
    (net (code "44") (name "/Ad33") (class "Default")
      (node (ref "K19") (pin "4") (pinfunction "4_4") (pintype "passive"))
      (node (ref "P5") (pin "18") (pinfunction "18_18") (pintype "passive"))
    )
    (net (code "45") (name "/Ad34") (class "Default")
      (node (ref "K20") (pin "4") (pinfunction "4_4") (pintype "passive"))
      (node (ref "P5") (pin "26") (pinfunction "26_26") (pintype "passive"))
    )
    (net (code "46") (name "/Ad35") (class "Default")
      (node (ref "K21") (pin "4") (pinfunction "4_4") (pintype "passive"))
      (node (ref "P6") (pin "1") (pinfunction "1_1") (pintype "passive"))
    )
    (net (code "47") (name "/Ad36") (class "Default")
      (node (ref "K22") (pin "4") (pinfunction "4_4") (pintype "passive"))
      (node (ref "P6") (pin "5") (pinfunction "5_5") (pintype "passive"))
    )
    (net (code "48") (name "/Ad37") (class "Default")
      (node (ref "K23") (pin "4") (pinfunction "4_4") (pintype "passive"))
      (node (ref "P6") (pin "9") (pinfunction "9_9") (pintype "passive"))
    )
    (net (code "49") (name "/Ad38") (class "Default")
      (node (ref "K24") (pin "4") (pinfunction "4_4") (pintype "passive"))
      (node (ref "P6") (pin "13") (pinfunction "13_13") (pintype "passive"))
    )
    (net (code "50") (name "/Ad41") (class "Default")
      (node (ref "K30") (pin "4") (pinfunction "4_4") (pintype "passive"))
      (node (ref "P11") (pin "2") (pinfunction "2_2") (pintype "passive"))
    )
    (net (code "51") (name "/Ad42") (class "Default")
      (node (ref "K29") (pin "4") (pinfunction "4_4") (pintype "passive"))
      (node (ref "P11") (pin "10") (pinfunction "10_10") (pintype "passive"))
    )
    (net (code "52") (name "/Ad43") (class "Default")
      (node (ref "K28") (pin "4") (pinfunction "4_4") (pintype "passive"))
      (node (ref "P11") (pin "18") (pinfunction "18_18") (pintype "passive"))
    )
    (net (code "53") (name "/Ad44") (class "Default")
      (node (ref "K27") (pin "4") (pinfunction "4_4") (pintype "passive"))
      (node (ref "P11") (pin "26") (pinfunction "26_26") (pintype "passive"))
    )
    (net (code "54") (name "/Ad45") (class "Default")
      (node (ref "K26") (pin "4") (pinfunction "4_4") (pintype "passive"))
      (node (ref "P11") (pin "34") (pinfunction "34_34") (pintype "passive"))
    )
    (net (code "55") (name "/Ad46") (class "Default")
      (node (ref "K25") (pin "4") (pinfunction "4_4") (pintype "passive"))
      (node (ref "P11") (pin "42") (pinfunction "42_42") (pintype "passive"))
    )
    (net (code "56") (name "/As11") (class "Default")
      (node (ref "P1") (pin "1") (pinfunction "1_1") (pintype "passive"))
      (node (ref "R1") (pin "2") (pintype "passive"))
    )
    (net (code "57") (name "/As12") (class "Default")
      (node (ref "P1") (pin "9") (pinfunction "9_9") (pintype "passive"))
      (node (ref "R3") (pin "2") (pintype "passive"))
    )
    (net (code "58") (name "/As13") (class "Default")
      (node (ref "P1") (pin "17") (pinfunction "17_17") (pintype "passive"))
      (node (ref "R5") (pin "2") (pintype "passive"))
    )
    (net (code "59") (name "/As14") (class "Default")
      (node (ref "P1") (pin "25") (pinfunction "25_25") (pintype "passive"))
      (node (ref "R7") (pin "2") (pintype "passive"))
    )
    (net (code "60") (name "/As18") (class "Default")
      (node (ref "P2") (pin "17") (pinfunction "17_17") (pintype "passive"))
      (node (ref "R9") (pin "2") (pintype "passive"))
    )
    (net (code "61") (name "/As21") (class "Default")
      (node (ref "P3") (pin "1") (pinfunction "1_1") (pintype "passive"))
      (node (ref "R27") (pin "2") (pintype "passive"))
    )
    (net (code "62") (name "/As22") (class "Default")
      (node (ref "P3") (pin "9") (pinfunction "9_9") (pintype "passive"))
      (node (ref "R29") (pin "2") (pintype "passive"))
    )
    (net (code "63") (name "/As23") (class "Default")
      (node (ref "P3") (pin "17") (pinfunction "17_17") (pintype "passive"))
      (node (ref "R31") (pin "2") (pintype "passive"))
    )
    (net (code "64") (name "/As24") (class "Default")
      (node (ref "P3") (pin "25") (pinfunction "25_25") (pintype "passive"))
      (node (ref "R33") (pin "2") (pintype "passive"))
    )
    (net (code "65") (name "/As28") (class "Default")
      (node (ref "P4") (pin "17") (pinfunction "17_17") (pintype "passive"))
      (node (ref "R35") (pin "2") (pintype "passive"))
    )
    (net (code "66") (name "/As31") (class "Default")
      (node (ref "P5") (pin "1") (pinfunction "1_1") (pintype "passive"))
      (node (ref "R53") (pin "2") (pintype "passive"))
    )
    (net (code "67") (name "/As32") (class "Default")
      (node (ref "P5") (pin "9") (pinfunction "9_9") (pintype "passive"))
      (node (ref "R55") (pin "2") (pintype "passive"))
    )
    (net (code "68") (name "/As33") (class "Default")
      (node (ref "P5") (pin "17") (pinfunction "17_17") (pintype "passive"))
      (node (ref "R57") (pin "2") (pintype "passive"))
    )
    (net (code "69") (name "/As34") (class "Default")
      (node (ref "P5") (pin "25") (pinfunction "25_25") (pintype "passive"))
      (node (ref "R59") (pin "2") (pintype "passive"))
    )
    (net (code "70") (name "/As38") (class "Default")
      (node (ref "P6") (pin "17") (pinfunction "17_17") (pintype "passive"))
      (node (ref "R61") (pin "2") (pintype "passive"))
    )
    (net (code "71") (name "/As41") (class "Default")
      (node (ref "K30") (pin "3") (pinfunction "3_3") (pintype "passive"))
      (node (ref "P11") (pin "1") (pinfunction "1_1") (pintype "passive"))
    )
    (net (code "72") (name "/As42") (class "Default")
      (node (ref "K29") (pin "3") (pinfunction "3_3") (pintype "passive"))
      (node (ref "P11") (pin "9") (pinfunction "9_9") (pintype "passive"))
    )
    (net (code "73") (name "/As43") (class "Default")
      (node (ref "K28") (pin "3") (pinfunction "3_3") (pintype "passive"))
      (node (ref "P11") (pin "17") (pinfunction "17_17") (pintype "passive"))
    )
    (net (code "74") (name "/As44") (class "Default")
      (node (ref "K27") (pin "3") (pinfunction "3_3") (pintype "passive"))
      (node (ref "P11") (pin "25") (pinfunction "25_25") (pintype "passive"))
    )
    (net (code "75") (name "/As45") (class "Default")
      (node (ref "K26") (pin "3") (pinfunction "3_3") (pintype "passive"))
      (node (ref "P11") (pin "33") (pinfunction "33_33") (pintype "passive"))
    )
    (net (code "76") (name "/As46") (class "Default")
      (node (ref "K25") (pin "3") (pinfunction "3_3") (pintype "passive"))
      (node (ref "P11") (pin "41") (pinfunction "41_41") (pintype "passive"))
    )
    (net (code "77") (name "/B1") (class "Default")
      (node (ref "K1") (pin "6") (pinfunction "6_6") (pintype "passive"))
      (node (ref "R18") (pin "1") (pintype "passive"))
      (node (ref "R2") (pin "1") (pintype "passive"))
      (node (ref "R26") (pin "2") (pintype "passive"))
    )
    (net (code "78") (name "/B2") (class "Default")
      (node (ref "K16") (pin "6") (pinfunction "6_6") (pintype "passive"))
      (node (ref "R26") (pin "1") (pintype "passive"))
      (node (ref "R36") (pin "1") (pintype "passive"))
      (node (ref "R51") (pin "2") (pintype "passive"))
    )
    (net (code "79") (name "/B22") (class "Default")
      (node (ref "K9") (pin "6") (pinfunction "6_6") (pintype "passive"))
      (node (ref "R28") (pin "1") (pintype "passive"))
      (node (ref "R45") (pin "1") (pintype "passive"))
      (node (ref "R86") (pin "2") (pintype "passive"))
    )
    (net (code "80") (name "/B23") (class "Default")
      (node (ref "K24") (pin "6") (pinfunction "6_6") (pintype "passive"))
      (node (ref "R62") (pin "1") (pintype "passive"))
      (node (ref "R76") (pin "2") (pintype "passive"))
      (node (ref "R86") (pin "1") (pintype "passive"))
    )
    (net (code "81") (name "/Bc11") (class "Default")
      (node (ref "K1") (pin "7") (pinfunction "7_7") (pintype "passive"))
      (node (ref "P1") (pin "7") (pinfunction "7_7") (pintype "passive"))
    )
    (net (code "82") (name "/Bc12") (class "Default")
      (node (ref "K2") (pin "7") (pinfunction "7_7") (pintype "passive"))
      (node (ref "P1") (pin "15") (pinfunction "15_15") (pintype "passive"))
    )
    (net (code "83") (name "/Bc13") (class "Default")
      (node (ref "K3") (pin "7") (pinfunction "7_7") (pintype "passive"))
      (node (ref "P1") (pin "23") (pinfunction "23_23") (pintype "passive"))
    )
    (net (code "84") (name "/Bc14") (class "Default")
      (node (ref "K4") (pin "7") (pinfunction "7_7") (pintype "passive"))
      (node (ref "P1") (pin "31") (pinfunction "31_31") (pintype "passive"))
    )
    (net (code "85") (name "/Bc21") (class "Default")
      (node (ref "K9") (pin "7") (pinfunction "7_7") (pintype "passive"))
      (node (ref "P3") (pin "7") (pinfunction "7_7") (pintype "passive"))
    )
    (net (code "86") (name "/Bc22") (class "Default")
      (node (ref "K10") (pin "7") (pinfunction "7_7") (pintype "passive"))
      (node (ref "P3") (pin "15") (pinfunction "15_15") (pintype "passive"))
    )
    (net (code "87") (name "/Bc23") (class "Default")
      (node (ref "K11") (pin "7") (pinfunction "7_7") (pintype "passive"))
      (node (ref "P3") (pin "23") (pinfunction "23_23") (pintype "passive"))
    )
    (net (code "88") (name "/Bc24") (class "Default")
      (node (ref "K12") (pin "7") (pinfunction "7_7") (pintype "passive"))
      (node (ref "P3") (pin "31") (pinfunction "31_31") (pintype "passive"))
    )
    (net (code "89") (name "/Bc31") (class "Default")
      (node (ref "K17") (pin "7") (pinfunction "7_7") (pintype "passive"))
      (node (ref "P5") (pin "7") (pinfunction "7_7") (pintype "passive"))
    )
    (net (code "90") (name "/Bc32") (class "Default")
      (node (ref "K18") (pin "7") (pinfunction "7_7") (pintype "passive"))
      (node (ref "P5") (pin "15") (pinfunction "15_15") (pintype "passive"))
    )
    (net (code "91") (name "/Bc33") (class "Default")
      (node (ref "K19") (pin "7") (pinfunction "7_7") (pintype "passive"))
      (node (ref "P5") (pin "23") (pinfunction "23_23") (pintype "passive"))
    )
    (net (code "92") (name "/Bc34") (class "Default")
      (node (ref "K20") (pin "7") (pinfunction "7_7") (pintype "passive"))
      (node (ref "P5") (pin "31") (pinfunction "31_31") (pintype "passive"))
    )
    (net (code "93") (name "/Bc41") (class "Default")
      (node (ref "K30") (pin "7") (pinfunction "7_7") (pintype "passive"))
      (node (ref "P11") (pin "7") (pinfunction "7_7") (pintype "passive"))
    )
    (net (code "94") (name "/Bc42") (class "Default")
      (node (ref "K29") (pin "7") (pinfunction "7_7") (pintype "passive"))
      (node (ref "P11") (pin "15") (pinfunction "15_15") (pintype "passive"))
    )
    (net (code "95") (name "/Bc43") (class "Default")
      (node (ref "K28") (pin "7") (pinfunction "7_7") (pintype "passive"))
      (node (ref "P11") (pin "23") (pinfunction "23_23") (pintype "passive"))
    )
    (net (code "96") (name "/Bc44") (class "Default")
      (node (ref "K27") (pin "7") (pinfunction "7_7") (pintype "passive"))
      (node (ref "P11") (pin "31") (pinfunction "31_31") (pintype "passive"))
    )
    (net (code "97") (name "/Bc45") (class "Default")
      (node (ref "K26") (pin "7") (pinfunction "7_7") (pintype "passive"))
      (node (ref "P11") (pin "39") (pinfunction "39_39") (pintype "passive"))
    )
    (net (code "98") (name "/Bc46") (class "Default")
      (node (ref "K25") (pin "7") (pinfunction "7_7") (pintype "passive"))
      (node (ref "P11") (pin "47") (pinfunction "47_47") (pintype "passive"))
    )
    (net (code "99") (name "/Bd11") (class "Default")
      (node (ref "K1") (pin "5") (pinfunction "5_5") (pintype "passive"))
      (node (ref "P1") (pin "6") (pinfunction "6_6") (pintype "passive"))
    )
    (net (code "100") (name "/Bd12") (class "Default")
      (node (ref "K2") (pin "5") (pinfunction "5_5") (pintype "passive"))
      (node (ref "P1") (pin "14") (pinfunction "14_14") (pintype "passive"))
    )
    (net (code "101") (name "/Bd13") (class "Default")
      (node (ref "K3") (pin "5") (pinfunction "5_5") (pintype "passive"))
      (node (ref "P1") (pin "22") (pinfunction "22_22") (pintype "passive"))
    )
    (net (code "102") (name "/Bd14") (class "Default")
      (node (ref "K4") (pin "5") (pinfunction "5_5") (pintype "passive"))
      (node (ref "P1") (pin "30") (pinfunction "30_30") (pintype "passive"))
    )
    (net (code "103") (name "/Bd15") (class "Default")
      (node (ref "K5") (pin "5") (pinfunction "5_5") (pintype "passive"))
      (node (ref "P2") (pin "3") (pinfunction "3_3") (pintype "passive"))
    )
    (net (code "104") (name "/Bd16") (class "Default")
      (node (ref "K6") (pin "5") (pinfunction "5_5") (pintype "passive"))
      (node (ref "P2") (pin "7") (pinfunction "7_7") (pintype "passive"))
    )
    (net (code "105") (name "/Bd17") (class "Default")
      (node (ref "K7") (pin "5") (pinfunction "5_5") (pintype "passive"))
      (node (ref "P2") (pin "11") (pinfunction "11_11") (pintype "passive"))
    )
    (net (code "106") (name "/Bd18") (class "Default")
      (node (ref "K8") (pin "5") (pinfunction "5_5") (pintype "passive"))
      (node (ref "P2") (pin "15") (pinfunction "15_15") (pintype "passive"))
    )
    (net (code "107") (name "/Bd21") (class "Default")
      (node (ref "K9") (pin "5") (pinfunction "5_5") (pintype "passive"))
      (node (ref "P3") (pin "6") (pinfunction "6_6") (pintype "passive"))
    )
    (net (code "108") (name "/Bd22") (class "Default")
      (node (ref "K10") (pin "5") (pinfunction "5_5") (pintype "passive"))
      (node (ref "P3") (pin "14") (pinfunction "14_14") (pintype "passive"))
    )
    (net (code "109") (name "/Bd23") (class "Default")
      (node (ref "K11") (pin "5") (pinfunction "5_5") (pintype "passive"))
      (node (ref "P3") (pin "22") (pinfunction "22_22") (pintype "passive"))
    )
    (net (code "110") (name "/Bd24") (class "Default")
      (node (ref "K12") (pin "5") (pinfunction "5_5") (pintype "passive"))
      (node (ref "P3") (pin "30") (pinfunction "30_30") (pintype "passive"))
    )
    (net (code "111") (name "/Bd25") (class "Default")
      (node (ref "K13") (pin "5") (pinfunction "5_5") (pintype "passive"))
      (node (ref "P4") (pin "3") (pinfunction "3_3") (pintype "passive"))
    )
    (net (code "112") (name "/Bd26") (class "Default")
      (node (ref "K14") (pin "5") (pinfunction "5_5") (pintype "passive"))
      (node (ref "P4") (pin "7") (pinfunction "7_7") (pintype "passive"))
    )
    (net (code "113") (name "/Bd27") (class "Default")
      (node (ref "K15") (pin "5") (pinfunction "5_5") (pintype "passive"))
      (node (ref "P4") (pin "11") (pinfunction "11_11") (pintype "passive"))
    )
    (net (code "114") (name "/Bd28") (class "Default")
      (node (ref "K16") (pin "5") (pinfunction "5_5") (pintype "passive"))
      (node (ref "P4") (pin "15") (pinfunction "15_15") (pintype "passive"))
    )
    (net (code "115") (name "/Bd31") (class "Default")
      (node (ref "K17") (pin "5") (pinfunction "5_5") (pintype "passive"))
      (node (ref "P5") (pin "6") (pinfunction "6_6") (pintype "passive"))
    )
    (net (code "116") (name "/Bd32") (class "Default")
      (node (ref "K18") (pin "5") (pinfunction "5_5") (pintype "passive"))
      (node (ref "P5") (pin "14") (pinfunction "14_14") (pintype "passive"))
    )
    (net (code "117") (name "/Bd33") (class "Default")
      (node (ref "K19") (pin "5") (pinfunction "5_5") (pintype "passive"))
      (node (ref "P5") (pin "22") (pinfunction "22_22") (pintype "passive"))
    )
    (net (code "118") (name "/Bd34") (class "Default")
      (node (ref "K20") (pin "5") (pinfunction "5_5") (pintype "passive"))
      (node (ref "P5") (pin "30") (pinfunction "30_30") (pintype "passive"))
    )
    (net (code "119") (name "/Bd35") (class "Default")
      (node (ref "K21") (pin "5") (pinfunction "5_5") (pintype "passive"))
      (node (ref "P6") (pin "3") (pinfunction "3_3") (pintype "passive"))
    )
    (net (code "120") (name "/Bd36") (class "Default")
      (node (ref "K22") (pin "5") (pinfunction "5_5") (pintype "passive"))
      (node (ref "P6") (pin "7") (pinfunction "7_7") (pintype "passive"))
    )
    (net (code "121") (name "/Bd37") (class "Default")
      (node (ref "K23") (pin "5") (pinfunction "5_5") (pintype "passive"))
      (node (ref "P6") (pin "11") (pinfunction "11_11") (pintype "passive"))
    )
    (net (code "122") (name "/Bd38") (class "Default")
      (node (ref "K24") (pin "5") (pinfunction "5_5") (pintype "passive"))
      (node (ref "P6") (pin "15") (pinfunction "15_15") (pintype "passive"))
    )
    (net (code "123") (name "/Bd41") (class "Default")
      (node (ref "K30") (pin "5") (pinfunction "5_5") (pintype "passive"))
      (node (ref "P11") (pin "6") (pinfunction "6_6") (pintype "passive"))
    )
    (net (code "124") (name "/Bd42") (class "Default")
      (node (ref "K29") (pin "5") (pinfunction "5_5") (pintype "passive"))
      (node (ref "P11") (pin "14") (pinfunction "14_14") (pintype "passive"))
    )
    (net (code "125") (name "/Bd43") (class "Default")
      (node (ref "K28") (pin "5") (pinfunction "5_5") (pintype "passive"))
      (node (ref "P11") (pin "22") (pinfunction "22_22") (pintype "passive"))
    )
    (net (code "126") (name "/Bd44") (class "Default")
      (node (ref "K27") (pin "5") (pinfunction "5_5") (pintype "passive"))
      (node (ref "P11") (pin "30") (pinfunction "30_30") (pintype "passive"))
    )
    (net (code "127") (name "/Bd45") (class "Default")
      (node (ref "K26") (pin "5") (pinfunction "5_5") (pintype "passive"))
      (node (ref "P11") (pin "38") (pinfunction "38_38") (pintype "passive"))
    )
    (net (code "128") (name "/Bd46") (class "Default")
      (node (ref "K25") (pin "5") (pinfunction "5_5") (pintype "passive"))
      (node (ref "P11") (pin "46") (pinfunction "46_46") (pintype "passive"))
    )
    (net (code "129") (name "/Bs11") (class "Default")
      (node (ref "P1") (pin "5") (pinfunction "5_5") (pintype "passive"))
      (node (ref "R2") (pin "2") (pintype "passive"))
    )
    (net (code "130") (name "/Bs12") (class "Default")
      (node (ref "P1") (pin "13") (pinfunction "13_13") (pintype "passive"))
      (node (ref "R4") (pin "2") (pintype "passive"))
    )
    (net (code "131") (name "/Bs13") (class "Default")
      (node (ref "P1") (pin "21") (pinfunction "21_21") (pintype "passive"))
      (node (ref "R6") (pin "2") (pintype "passive"))
    )
    (net (code "132") (name "/Bs14") (class "Default")
      (node (ref "P1") (pin "29") (pinfunction "29_29") (pintype "passive"))
      (node (ref "R8") (pin "2") (pintype "passive"))
    )
    (net (code "133") (name "/Bs18") (class "Default")
      (node (ref "P2") (pin "19") (pinfunction "19_19") (pintype "passive"))
      (node (ref "R10") (pin "2") (pintype "passive"))
    )
    (net (code "134") (name "/Bs21") (class "Default")
      (node (ref "P3") (pin "5") (pinfunction "5_5") (pintype "passive"))
      (node (ref "R28") (pin "2") (pintype "passive"))
    )
    (net (code "135") (name "/Bs22") (class "Default")
      (node (ref "P3") (pin "13") (pinfunction "13_13") (pintype "passive"))
      (node (ref "R30") (pin "2") (pintype "passive"))
    )
    (net (code "136") (name "/Bs23") (class "Default")
      (node (ref "P3") (pin "21") (pinfunction "21_21") (pintype "passive"))
      (node (ref "R32") (pin "2") (pintype "passive"))
    )
    (net (code "137") (name "/Bs24") (class "Default")
      (node (ref "P3") (pin "29") (pinfunction "29_29") (pintype "passive"))
      (node (ref "R34") (pin "2") (pintype "passive"))
    )
    (net (code "138") (name "/Bs28") (class "Default")
      (node (ref "P4") (pin "19") (pinfunction "19_19") (pintype "passive"))
      (node (ref "R36") (pin "2") (pintype "passive"))
    )
    (net (code "139") (name "/Bs31") (class "Default")
      (node (ref "P5") (pin "5") (pinfunction "5_5") (pintype "passive"))
      (node (ref "R54") (pin "2") (pintype "passive"))
    )
    (net (code "140") (name "/Bs32") (class "Default")
      (node (ref "P5") (pin "13") (pinfunction "13_13") (pintype "passive"))
      (node (ref "R56") (pin "2") (pintype "passive"))
    )
    (net (code "141") (name "/Bs33") (class "Default")
      (node (ref "P5") (pin "21") (pinfunction "21_21") (pintype "passive"))
      (node (ref "R58") (pin "2") (pintype "passive"))
    )
    (net (code "142") (name "/Bs34") (class "Default")
      (node (ref "P5") (pin "29") (pinfunction "29_29") (pintype "passive"))
      (node (ref "R60") (pin "2") (pintype "passive"))
    )
    (net (code "143") (name "/Bs38") (class "Default")
      (node (ref "P6") (pin "19") (pinfunction "19_19") (pintype "passive"))
      (node (ref "R62") (pin "2") (pintype "passive"))
    )
    (net (code "144") (name "/Bs41") (class "Default")
      (node (ref "K30") (pin "6") (pinfunction "6_6") (pintype "passive"))
      (node (ref "P11") (pin "5") (pinfunction "5_5") (pintype "passive"))
    )
    (net (code "145") (name "/Bs42") (class "Default")
      (node (ref "K29") (pin "6") (pinfunction "6_6") (pintype "passive"))
      (node (ref "P11") (pin "13") (pinfunction "13_13") (pintype "passive"))
    )
    (net (code "146") (name "/Bs43") (class "Default")
      (node (ref "K28") (pin "6") (pinfunction "6_6") (pintype "passive"))
      (node (ref "P11") (pin "21") (pinfunction "21_21") (pintype "passive"))
    )
    (net (code "147") (name "/Bs44") (class "Default")
      (node (ref "K27") (pin "6") (pinfunction "6_6") (pintype "passive"))
      (node (ref "P11") (pin "29") (pinfunction "29_29") (pintype "passive"))
    )
    (net (code "148") (name "/Bs45") (class "Default")
      (node (ref "K26") (pin "6") (pinfunction "6_6") (pintype "passive"))
      (node (ref "P11") (pin "37") (pinfunction "37_37") (pintype "passive"))
    )
    (net (code "149") (name "/Bs46") (class "Default")
      (node (ref "K25") (pin "6") (pinfunction "6_6") (pintype "passive"))
      (node (ref "P11") (pin "45") (pinfunction "45_45") (pintype "passive"))
    )
    (net (code "150") (name "/INT") (class "Default")
      (node (ref "P10") (pin "12") (pinfunction "12_12") (pintype "passive"))
      (node (ref "P9") (pin "12") (pinfunction "12_12") (pintype "passive"))
      (node (ref "R80") (pin "1") (pintype "passive"))
      (node (ref "R82") (pin "2") (pintype "passive"))
    )
    (net (code "151") (name "/MISO") (class "Default")
      (node (ref "J1") (pin "2") (pinfunction "2_2") (pintype "passive"))
      (node (ref "P10") (pin "2") (pinfunction "2_2") (pintype "passive"))
      (node (ref "P9") (pin "2") (pinfunction "2_2") (pintype "passive"))
    )
    (net (code "152") (name "/MISO_T88") (class "Default")
      (node (ref "J1") (pin "1") (pinfunction "1_1") (pintype "passive"))
      (node (ref "P10") (pin "4") (pinfunction "4_4") (pintype "passive"))
      (node (ref "U1") (pin "14") (pinfunction "PB4_(MISO/PCINT4)_14") (pintype "bidirectional"))
    )
    (net (code "153") (name "/MOSI_T88") (class "Default")
      (node (ref "P9") (pin "4") (pinfunction "4_4") (pintype "passive"))
      (node (ref "R78") (pin "1") (pintype "passive"))
    )
    (net (code "154") (name "/R11") (class "Default")
      (node (ref "K1") (pin "8") (pinfunction "8_8") (pintype "passive"))
      (node (ref "ULN1") (pin "10") (pinfunction "C8_10") (pintype "passive"))
    )
    (net (code "155") (name "/R12") (class "Default")
      (node (ref "K2") (pin "8") (pinfunction "8_8") (pintype "passive"))
      (node (ref "ULN1") (pin "11") (pinfunction "C7_11") (pintype "passive"))
    )
    (net (code "156") (name "/R13") (class "Default")
      (node (ref "K3") (pin "8") (pinfunction "8_8") (pintype "passive"))
      (node (ref "ULN1") (pin "12") (pinfunction "C6_12") (pintype "passive"))
    )
    (net (code "157") (name "/R14") (class "Default")
      (node (ref "K4") (pin "8") (pinfunction "8_8") (pintype "passive"))
      (node (ref "ULN1") (pin "13") (pinfunction "C5_13") (pintype "passive"))
    )
    (net (code "158") (name "/R15") (class "Default")
      (node (ref "K5") (pin "8") (pinfunction "8_8") (pintype "passive"))
      (node (ref "ULN1") (pin "14") (pinfunction "C4_14") (pintype "passive"))
    )
    (net (code "159") (name "/R16") (class "Default")
      (node (ref "K6") (pin "8") (pinfunction "8_8") (pintype "passive"))
      (node (ref "ULN1") (pin "15") (pinfunction "C3_15") (pintype "passive"))
    )
    (net (code "160") (name "/R17") (class "Default")
      (node (ref "K7") (pin "8") (pinfunction "8_8") (pintype "passive"))
      (node (ref "ULN1") (pin "16") (pinfunction "C2_16") (pintype "passive"))
    )
    (net (code "161") (name "/R18") (class "Default")
      (node (ref "K8") (pin "8") (pinfunction "8_8") (pintype "passive"))
      (node (ref "ULN1") (pin "17") (pinfunction "C1_17") (pintype "passive"))
    )
    (net (code "162") (name "/R21") (class "Default")
      (node (ref "K9") (pin "8") (pinfunction "8_8") (pintype "passive"))
      (node (ref "ULN2") (pin "10") (pinfunction "C8_10") (pintype "passive"))
    )
    (net (code "163") (name "/R22") (class "Default")
      (node (ref "K10") (pin "8") (pinfunction "8_8") (pintype "passive"))
      (node (ref "ULN2") (pin "11") (pinfunction "C7_11") (pintype "passive"))
    )
    (net (code "164") (name "/R23") (class "Default")
      (node (ref "K11") (pin "8") (pinfunction "8_8") (pintype "passive"))
      (node (ref "ULN2") (pin "12") (pinfunction "C6_12") (pintype "passive"))
    )
    (net (code "165") (name "/R24") (class "Default")
      (node (ref "K12") (pin "8") (pinfunction "8_8") (pintype "passive"))
      (node (ref "ULN2") (pin "13") (pinfunction "C5_13") (pintype "passive"))
    )
    (net (code "166") (name "/R25") (class "Default")
      (node (ref "K13") (pin "8") (pinfunction "8_8") (pintype "passive"))
      (node (ref "ULN2") (pin "14") (pinfunction "C4_14") (pintype "passive"))
    )
    (net (code "167") (name "/R26") (class "Default")
      (node (ref "K14") (pin "8") (pinfunction "8_8") (pintype "passive"))
      (node (ref "ULN2") (pin "15") (pinfunction "C3_15") (pintype "passive"))
    )
    (net (code "168") (name "/R27") (class "Default")
      (node (ref "K15") (pin "8") (pinfunction "8_8") (pintype "passive"))
      (node (ref "ULN2") (pin "16") (pinfunction "C2_16") (pintype "passive"))
    )
    (net (code "169") (name "/R28") (class "Default")
      (node (ref "K16") (pin "8") (pinfunction "8_8") (pintype "passive"))
      (node (ref "ULN2") (pin "17") (pinfunction "C1_17") (pintype "passive"))
    )
    (net (code "170") (name "/R31") (class "Default")
      (node (ref "K17") (pin "8") (pinfunction "8_8") (pintype "passive"))
      (node (ref "ULN3") (pin "10") (pinfunction "C8_10") (pintype "passive"))
    )
    (net (code "171") (name "/R32") (class "Default")
      (node (ref "K18") (pin "8") (pinfunction "8_8") (pintype "passive"))
      (node (ref "ULN3") (pin "11") (pinfunction "C7_11") (pintype "passive"))
    )
    (net (code "172") (name "/R33") (class "Default")
      (node (ref "K19") (pin "8") (pinfunction "8_8") (pintype "passive"))
      (node (ref "ULN3") (pin "12") (pinfunction "C6_12") (pintype "passive"))
    )
    (net (code "173") (name "/R34") (class "Default")
      (node (ref "K20") (pin "8") (pinfunction "8_8") (pintype "passive"))
      (node (ref "ULN3") (pin "13") (pinfunction "C5_13") (pintype "passive"))
    )
    (net (code "174") (name "/R35") (class "Default")
      (node (ref "K21") (pin "8") (pinfunction "8_8") (pintype "passive"))
      (node (ref "ULN3") (pin "14") (pinfunction "C4_14") (pintype "passive"))
    )
    (net (code "175") (name "/R36") (class "Default")
      (node (ref "K22") (pin "8") (pinfunction "8_8") (pintype "passive"))
      (node (ref "ULN3") (pin "15") (pinfunction "C3_15") (pintype "passive"))
    )
    (net (code "176") (name "/R37") (class "Default")
      (node (ref "K23") (pin "8") (pinfunction "8_8") (pintype "passive"))
      (node (ref "ULN3") (pin "16") (pinfunction "C2_16") (pintype "passive"))
    )
    (net (code "177") (name "/R38") (class "Default")
      (node (ref "K24") (pin "8") (pinfunction "8_8") (pintype "passive"))
      (node (ref "ULN3") (pin "17") (pinfunction "C1_17") (pintype "passive"))
    )
    (net (code "178") (name "/R41") (class "Default")
      (node (ref "K30") (pin "8") (pinfunction "8_8") (pintype "passive"))
      (node (ref "ULN4") (pin "12") (pinfunction "C6_12") (pintype "passive"))
    )
    (net (code "179") (name "/R42") (class "Default")
      (node (ref "K29") (pin "8") (pinfunction "8_8") (pintype "passive"))
      (node (ref "ULN4") (pin "13") (pinfunction "C5_13") (pintype "passive"))
    )
    (net (code "180") (name "/R43") (class "Default")
      (node (ref "K28") (pin "8") (pinfunction "8_8") (pintype "passive"))
      (node (ref "ULN4") (pin "14") (pinfunction "C4_14") (pintype "passive"))
    )
    (net (code "181") (name "/R44") (class "Default")
      (node (ref "K27") (pin "8") (pinfunction "8_8") (pintype "passive"))
      (node (ref "ULN4") (pin "15") (pinfunction "C3_15") (pintype "passive"))
    )
    (net (code "182") (name "/R45") (class "Default")
      (node (ref "K26") (pin "8") (pinfunction "8_8") (pintype "passive"))
      (node (ref "ULN4") (pin "16") (pinfunction "C2_16") (pintype "passive"))
    )
    (net (code "183") (name "/R46") (class "Default")
      (node (ref "K25") (pin "8") (pinfunction "8_8") (pintype "passive"))
      (node (ref "ULN4") (pin "17") (pinfunction "C1_17") (pintype "passive"))
    )
    (net (code "184") (name "/SCK") (class "Default")
      (node (ref "P10") (pin "6") (pinfunction "6_6") (pintype "passive"))
      (node (ref "P9") (pin "6") (pinfunction "6_6") (pintype "passive"))
      (node (ref "R79") (pin "1") (pintype "passive"))
    )
    (net (code "185") (name "/SCL") (class "Default")
      (node (ref "MCP1") (pin "8") (pinfunction "SCL_8") (pintype "passive"))
      (node (ref "MCP2") (pin "8") (pinfunction "SCL_8") (pintype "passive"))
      (node (ref "R84") (pin "2") (pintype "passive"))
      (node (ref "U1") (pin "24") (pinfunction "PC5_(ADC5/SCL/PCINT13)_24") (pintype "bidirectional"))
    )
    (net (code "186") (name "/SDA") (class "Default")
      (node (ref "MCP1") (pin "9") (pinfunction "SDA_9") (pintype "passive"))
      (node (ref "MCP2") (pin "9") (pinfunction "SDA_9") (pintype "passive"))
      (node (ref "R83") (pin "2") (pintype "passive"))
      (node (ref "U1") (pin "23") (pinfunction "PC4_(ADC4/SDA/PCINT12)_23") (pintype "bidirectional"))
    )
    (net (code "187") (name "/~{RESET}") (class "Default")
      (node (ref "P10") (pin "10") (pinfunction "10_10") (pintype "passive"))
      (node (ref "P9") (pin "10") (pinfunction "10_10") (pintype "passive"))
      (node (ref "R81") (pin "2") (pintype "passive"))
      (node (ref "U1") (pin "25") (pinfunction "PC6_(PCINT14/~{RESET})_25") (pintype "bidirectional"))
    )
    (net (code "188") (name "/~{SS}") (class "Default")
      (node (ref "P10") (pin "8") (pinfunction "8_8") (pintype "passive"))
      (node (ref "P9") (pin "8") (pinfunction "8_8") (pintype "passive"))
      (node (ref "R77") (pin "1") (pintype "passive"))
    )
    (net (code "189") (name "AGND1") (class "Default")
      (node (ref "P1") (pin "12") (pinfunction "12_12") (pintype "passive"))
      (node (ref "P1") (pin "16") (pinfunction "16_16") (pintype "passive"))
      (node (ref "P1") (pin "20") (pinfunction "20_20") (pintype "passive"))
      (node (ref "P1") (pin "24") (pinfunction "24_24") (pintype "passive"))
      (node (ref "P1") (pin "28") (pinfunction "28_28") (pintype "passive"))
      (node (ref "P1") (pin "32") (pinfunction "32_32") (pintype "passive"))
      (node (ref "P1") (pin "4") (pinfunction "4_4") (pintype "passive"))
      (node (ref "P1") (pin "8") (pinfunction "8_8") (pintype "passive"))
      (node (ref "P2") (pin "10") (pinfunction "10_10") (pintype "passive"))
      (node (ref "P2") (pin "12") (pinfunction "12_12") (pintype "passive"))
      (node (ref "P2") (pin "14") (pinfunction "14_14") (pintype "passive"))
      (node (ref "P2") (pin "16") (pinfunction "16_16") (pintype "passive"))
      (node (ref "P2") (pin "18") (pinfunction "18_18") (pintype "passive"))
      (node (ref "P2") (pin "2") (pinfunction "2_2") (pintype "passive"))
      (node (ref "P2") (pin "20") (pinfunction "20_20") (pintype "passive"))
      (node (ref "P2") (pin "4") (pinfunction "4_4") (pintype "passive"))
      (node (ref "P2") (pin "6") (pinfunction "6_6") (pintype "passive"))
      (node (ref "P2") (pin "8") (pinfunction "8_8") (pintype "passive"))
    )
    (net (code "190") (name "AGND2") (class "Default")
      (node (ref "P3") (pin "12") (pinfunction "12_12") (pintype "passive"))
      (node (ref "P3") (pin "16") (pinfunction "16_16") (pintype "passive"))
      (node (ref "P3") (pin "20") (pinfunction "20_20") (pintype "passive"))
      (node (ref "P3") (pin "24") (pinfunction "24_24") (pintype "passive"))
      (node (ref "P3") (pin "28") (pinfunction "28_28") (pintype "passive"))
      (node (ref "P3") (pin "32") (pinfunction "32_32") (pintype "passive"))
      (node (ref "P3") (pin "4") (pinfunction "4_4") (pintype "passive"))
      (node (ref "P3") (pin "8") (pinfunction "8_8") (pintype "passive"))
      (node (ref "P4") (pin "10") (pinfunction "10_10") (pintype "passive"))
      (node (ref "P4") (pin "12") (pinfunction "12_12") (pintype "passive"))
      (node (ref "P4") (pin "14") (pinfunction "14_14") (pintype "passive"))
      (node (ref "P4") (pin "16") (pinfunction "16_16") (pintype "passive"))
      (node (ref "P4") (pin "18") (pinfunction "18_18") (pintype "passive"))
      (node (ref "P4") (pin "2") (pinfunction "2_2") (pintype "passive"))
      (node (ref "P4") (pin "20") (pinfunction "20_20") (pintype "passive"))
      (node (ref "P4") (pin "4") (pinfunction "4_4") (pintype "passive"))
      (node (ref "P4") (pin "6") (pinfunction "6_6") (pintype "passive"))
      (node (ref "P4") (pin "8") (pinfunction "8_8") (pintype "passive"))
    )
    (net (code "191") (name "AGND3") (class "Default")
      (node (ref "P5") (pin "12") (pinfunction "12_12") (pintype "passive"))
      (node (ref "P5") (pin "16") (pinfunction "16_16") (pintype "passive"))
      (node (ref "P5") (pin "20") (pinfunction "20_20") (pintype "passive"))
      (node (ref "P5") (pin "24") (pinfunction "24_24") (pintype "passive"))
      (node (ref "P5") (pin "28") (pinfunction "28_28") (pintype "passive"))
      (node (ref "P5") (pin "32") (pinfunction "32_32") (pintype "passive"))
      (node (ref "P5") (pin "4") (pinfunction "4_4") (pintype "passive"))
      (node (ref "P5") (pin "8") (pinfunction "8_8") (pintype "passive"))
      (node (ref "P6") (pin "10") (pinfunction "10_10") (pintype "passive"))
      (node (ref "P6") (pin "12") (pinfunction "12_12") (pintype "passive"))
      (node (ref "P6") (pin "14") (pinfunction "14_14") (pintype "passive"))
      (node (ref "P6") (pin "16") (pinfunction "16_16") (pintype "passive"))
      (node (ref "P6") (pin "18") (pinfunction "18_18") (pintype "passive"))
      (node (ref "P6") (pin "2") (pinfunction "2_2") (pintype "passive"))
      (node (ref "P6") (pin "20") (pinfunction "20_20") (pintype "passive"))
      (node (ref "P6") (pin "4") (pinfunction "4_4") (pintype "passive"))
      (node (ref "P6") (pin "6") (pinfunction "6_6") (pintype "passive"))
      (node (ref "P6") (pin "8") (pinfunction "8_8") (pintype "passive"))
    )
    (net (code "192") (name "AGND4") (class "Default")
      (node (ref "P11") (pin "12") (pinfunction "12_12") (pintype "passive"))
      (node (ref "P11") (pin "16") (pinfunction "16_16") (pintype "passive"))
      (node (ref "P11") (pin "20") (pinfunction "20_20") (pintype "passive"))
      (node (ref "P11") (pin "24") (pinfunction "24_24") (pintype "passive"))
      (node (ref "P11") (pin "28") (pinfunction "28_28") (pintype "passive"))
      (node (ref "P11") (pin "32") (pinfunction "32_32") (pintype "passive"))
      (node (ref "P11") (pin "36") (pinfunction "36_36") (pintype "passive"))
      (node (ref "P11") (pin "4") (pinfunction "4_4") (pintype "passive"))
      (node (ref "P11") (pin "40") (pinfunction "40_40") (pintype "passive"))
      (node (ref "P11") (pin "44") (pinfunction "44_44") (pintype "passive"))
      (node (ref "P11") (pin "48") (pinfunction "48_48") (pintype "passive"))
      (node (ref "P11") (pin "8") (pinfunction "8_8") (pintype "passive"))
    )
    (net (code "193") (name "AVCC") (class "Default")
      (node (ref "C15") (pin "1") (pinfunction "1_1") (pintype "passive"))
      (node (ref "FB1") (pin "2") (pintype "passive"))
      (node (ref "U1") (pin "16") (pinfunction "AVCC_16") (pintype "power_in"))
    )
    (net (code "194") (name "GND") (class "Default")
      (node (ref "C1") (pin "1") (pinfunction "1_1") (pintype "passive"))
      (node (ref "C10") (pin "2") (pinfunction "2_2") (pintype "passive"))
      (node (ref "C11") (pin "2") (pinfunction "2_2") (pintype "passive"))
      (node (ref "C12") (pin "2") (pinfunction "2_2") (pintype "passive"))
      (node (ref "C13") (pin "2") (pinfunction "2_2") (pintype "passive"))
      (node (ref "C14") (pin "2") (pinfunction "2_2") (pintype "passive"))
      (node (ref "C15") (pin "2") (pinfunction "2_2") (pintype "passive"))
      (node (ref "C2") (pin "1") (pinfunction "1_1") (pintype "passive"))
      (node (ref "C3") (pin "2") (pinfunction "2_2") (pintype "passive"))
      (node (ref "C4") (pin "2") (pinfunction "2_2") (pintype "passive"))
      (node (ref "C5") (pin "1") (pinfunction "1_1") (pintype "passive"))
      (node (ref "C6") (pin "1") (pinfunction "1_1") (pintype "passive"))
      (node (ref "C7") (pin "2") (pinfunction "2_2") (pintype "passive"))
      (node (ref "C8") (pin "2") (pinfunction "2_2") (pintype "passive"))
      (node (ref "C9") (pin "2") (pinfunction "2_2") (pintype "passive"))
      (node (ref "LD1") (pin "2") (pinfunction "GND_2") (pintype "passive"))
      (node (ref "MCP1") (pin "12") (pinfunction "A1_12") (pintype "passive"))
      (node (ref "MCP1") (pin "13") (pinfunction "A2_13") (pintype "passive"))
      (node (ref "MCP1") (pin "6") (pinfunction "GND_6") (pintype "passive"))
      (node (ref "MCP2") (pin "11") (pinfunction "A0_11") (pintype "passive"))
      (node (ref "MCP2") (pin "12") (pinfunction "A1_12") (pintype "passive"))
      (node (ref "MCP2") (pin "13") (pinfunction "A2_13") (pintype "passive"))
      (node (ref "MCP2") (pin "6") (pinfunction "GND_6") (pintype "passive"))
      (node (ref "P10") (pin "1") (pinfunction "1_1") (pintype "passive"))
      (node (ref "P10") (pin "11") (pinfunction "11_11") (pintype "passive"))
      (node (ref "P10") (pin "3") (pinfunction "3_3") (pintype "passive"))
      (node (ref "P10") (pin "5") (pinfunction "5_5") (pintype "passive"))
      (node (ref "P10") (pin "7") (pinfunction "7_7") (pintype "passive"))
      (node (ref "P10") (pin "9") (pinfunction "9_9") (pintype "passive"))
      (node (ref "P7") (pin "1") (pinfunction "1_1") (pintype "passive"))
      (node (ref "P7") (pin "4") (pinfunction "4_4") (pintype "passive"))
      (node (ref "P8") (pin "1") (pinfunction "1_1") (pintype "passive"))
      (node (ref "P8") (pin "4") (pinfunction "4_4") (pintype "passive"))
      (node (ref "P9") (pin "1") (pinfunction "1_1") (pintype "passive"))
      (node (ref "P9") (pin "11") (pinfunction "11_11") (pintype "passive"))
      (node (ref "P9") (pin "3") (pinfunction "3_3") (pintype "passive"))
      (node (ref "P9") (pin "5") (pinfunction "5_5") (pintype "passive"))
      (node (ref "P9") (pin "7") (pinfunction "7_7") (pintype "passive"))
      (node (ref "P9") (pin "9") (pinfunction "9_9") (pintype "passive"))
      (node (ref "U1") (pin "18") (pinfunction "GND_18") (pintype "power_in"))
      (node (ref "U1") (pin "29") (pinfunction "DAP_29") (pintype "passive"))
      (node (ref "U1") (pin "4") (pinfunction "GND_4") (pintype "power_in"))
      (node (ref "ULN1") (pin "21") (pinfunction "PAD_21") (pintype "passive"))
      (node (ref "ULN1") (pin "8") (pinfunction "GND_8") (pintype "passive"))
      (node (ref "ULN2") (pin "21") (pinfunction "PAD_21") (pintype "passive"))
      (node (ref "ULN2") (pin "8") (pinfunction "GND_8") (pintype "passive"))
      (node (ref "ULN3") (pin "21") (pinfunction "PAD_21") (pintype "passive"))
      (node (ref "ULN3") (pin "8") (pinfunction "GND_8") (pintype "passive"))
      (node (ref "ULN4") (pin "21") (pinfunction "PAD_21") (pintype "passive"))
      (node (ref "ULN4") (pin "8") (pinfunction "GND_8") (pintype "passive"))
    )
    (net (code "195") (name "Net-(K2-Pad3)") (class "Default")
      (node (ref "K2") (pin "3") (pinfunction "3_3") (pintype "passive"))
      (node (ref "R11") (pin "2") (pintype "passive"))
      (node (ref "R12") (pin "1") (pintype "passive"))
      (node (ref "R3") (pin "1") (pintype "passive"))
    )
    (net (code "196") (name "Net-(K2-Pad6)") (class "Default")
      (node (ref "K2") (pin "6") (pinfunction "6_6") (pintype "passive"))
      (node (ref "R18") (pin "2") (pintype "passive"))
      (node (ref "R19") (pin "1") (pintype "passive"))
      (node (ref "R4") (pin "1") (pintype "passive"))
    )
    (net (code "197") (name "Net-(K3-Pad3)") (class "Default")
      (node (ref "K3") (pin "3") (pinfunction "3_3") (pintype "passive"))
      (node (ref "R12") (pin "2") (pintype "passive"))
      (node (ref "R13") (pin "1") (pintype "passive"))
      (node (ref "R5") (pin "1") (pintype "passive"))
    )
    (net (code "198") (name "Net-(K3-Pad6)") (class "Default")
      (node (ref "K3") (pin "6") (pinfunction "6_6") (pintype "passive"))
      (node (ref "R19") (pin "2") (pintype "passive"))
      (node (ref "R20") (pin "1") (pintype "passive"))
      (node (ref "R6") (pin "1") (pintype "passive"))
    )
    (net (code "199") (name "Net-(K4-Pad3)") (class "Default")
      (node (ref "K4") (pin "3") (pinfunction "3_3") (pintype "passive"))
      (node (ref "R13") (pin "2") (pintype "passive"))
      (node (ref "R14") (pin "1") (pintype "passive"))
      (node (ref "R7") (pin "1") (pintype "passive"))
    )
    (net (code "200") (name "Net-(K4-Pad6)") (class "Default")
      (node (ref "K4") (pin "6") (pinfunction "6_6") (pintype "passive"))
      (node (ref "R20") (pin "2") (pintype "passive"))
      (node (ref "R21") (pin "1") (pintype "passive"))
      (node (ref "R8") (pin "1") (pintype "passive"))
    )
    (net (code "201") (name "Net-(K5-Pad3)") (class "Default")
      (node (ref "K5") (pin "3") (pinfunction "3_3") (pintype "passive"))
      (node (ref "R14") (pin "2") (pintype "passive"))
      (node (ref "R15") (pin "1") (pintype "passive"))
    )
    (net (code "202") (name "Net-(K5-Pad6)") (class "Default")
      (node (ref "K5") (pin "6") (pinfunction "6_6") (pintype "passive"))
      (node (ref "R21") (pin "2") (pintype "passive"))
      (node (ref "R22") (pin "1") (pintype "passive"))
    )
    (net (code "203") (name "Net-(K6-Pad3)") (class "Default")
      (node (ref "K6") (pin "3") (pinfunction "3_3") (pintype "passive"))
      (node (ref "R15") (pin "2") (pintype "passive"))
      (node (ref "R16") (pin "1") (pintype "passive"))
    )
    (net (code "204") (name "Net-(K6-Pad6)") (class "Default")
      (node (ref "K6") (pin "6") (pinfunction "6_6") (pintype "passive"))
      (node (ref "R22") (pin "2") (pintype "passive"))
      (node (ref "R23") (pin "1") (pintype "passive"))
    )
    (net (code "205") (name "Net-(K7-Pad3)") (class "Default")
      (node (ref "K7") (pin "3") (pinfunction "3_3") (pintype "passive"))
      (node (ref "R16") (pin "2") (pintype "passive"))
      (node (ref "R17") (pin "1") (pintype "passive"))
    )
    (net (code "206") (name "Net-(K7-Pad6)") (class "Default")
      (node (ref "K7") (pin "6") (pinfunction "6_6") (pintype "passive"))
      (node (ref "R23") (pin "2") (pintype "passive"))
      (node (ref "R24") (pin "1") (pintype "passive"))
    )
    (net (code "207") (name "Net-(K8-Pad3)") (class "Default")
      (node (ref "K8") (pin "3") (pinfunction "3_3") (pintype "passive"))
      (node (ref "R17") (pin "2") (pintype "passive"))
      (node (ref "R9") (pin "1") (pintype "passive"))
    )
    (net (code "208") (name "Net-(K8-Pad6)") (class "Default")
      (node (ref "K8") (pin "6") (pinfunction "6_6") (pintype "passive"))
      (node (ref "R10") (pin "1") (pintype "passive"))
      (node (ref "R24") (pin "2") (pintype "passive"))
    )
    (net (code "209") (name "Net-(K10-Pad3)") (class "Default")
      (node (ref "K10") (pin "3") (pinfunction "3_3") (pintype "passive"))
      (node (ref "R29") (pin "1") (pintype "passive"))
      (node (ref "R38") (pin "2") (pintype "passive"))
      (node (ref "R39") (pin "1") (pintype "passive"))
    )
    (net (code "210") (name "Net-(K10-Pad6)") (class "Default")
      (node (ref "K10") (pin "6") (pinfunction "6_6") (pintype "passive"))
      (node (ref "R30") (pin "1") (pintype "passive"))
      (node (ref "R45") (pin "2") (pintype "passive"))
      (node (ref "R46") (pin "1") (pintype "passive"))
    )
    (net (code "211") (name "Net-(K11-Pad3)") (class "Default")
      (node (ref "K11") (pin "3") (pinfunction "3_3") (pintype "passive"))
      (node (ref "R31") (pin "1") (pintype "passive"))
      (node (ref "R39") (pin "2") (pintype "passive"))
      (node (ref "R40") (pin "1") (pintype "passive"))
    )
    (net (code "212") (name "Net-(K11-Pad6)") (class "Default")
      (node (ref "K11") (pin "6") (pinfunction "6_6") (pintype "passive"))
      (node (ref "R32") (pin "1") (pintype "passive"))
      (node (ref "R46") (pin "2") (pintype "passive"))
      (node (ref "R47") (pin "1") (pintype "passive"))
    )
    (net (code "213") (name "Net-(K12-Pad3)") (class "Default")
      (node (ref "K12") (pin "3") (pinfunction "3_3") (pintype "passive"))
      (node (ref "R33") (pin "1") (pintype "passive"))
      (node (ref "R40") (pin "2") (pintype "passive"))
      (node (ref "R41") (pin "1") (pintype "passive"))
    )
    (net (code "214") (name "Net-(K12-Pad6)") (class "Default")
      (node (ref "K12") (pin "6") (pinfunction "6_6") (pintype "passive"))
      (node (ref "R34") (pin "1") (pintype "passive"))
      (node (ref "R47") (pin "2") (pintype "passive"))
      (node (ref "R48") (pin "1") (pintype "passive"))
    )
    (net (code "215") (name "Net-(K13-Pad3)") (class "Default")
      (node (ref "K13") (pin "3") (pinfunction "3_3") (pintype "passive"))
      (node (ref "R41") (pin "2") (pintype "passive"))
      (node (ref "R42") (pin "1") (pintype "passive"))
    )
    (net (code "216") (name "Net-(K13-Pad6)") (class "Default")
      (node (ref "K13") (pin "6") (pinfunction "6_6") (pintype "passive"))
      (node (ref "R48") (pin "2") (pintype "passive"))
      (node (ref "R49") (pin "1") (pintype "passive"))
    )
    (net (code "217") (name "Net-(K14-Pad3)") (class "Default")
      (node (ref "K14") (pin "3") (pinfunction "3_3") (pintype "passive"))
      (node (ref "R42") (pin "2") (pintype "passive"))
      (node (ref "R43") (pin "1") (pintype "passive"))
    )
    (net (code "218") (name "Net-(K14-Pad6)") (class "Default")
      (node (ref "K14") (pin "6") (pinfunction "6_6") (pintype "passive"))
      (node (ref "R49") (pin "2") (pintype "passive"))
      (node (ref "R50") (pin "1") (pintype "passive"))
    )
    (net (code "219") (name "Net-(K15-Pad3)") (class "Default")
      (node (ref "K15") (pin "3") (pinfunction "3_3") (pintype "passive"))
      (node (ref "R43") (pin "2") (pintype "passive"))
      (node (ref "R44") (pin "1") (pintype "passive"))
    )
    (net (code "220") (name "Net-(K15-Pad6)") (class "Default")
      (node (ref "K15") (pin "6") (pinfunction "6_6") (pintype "passive"))
      (node (ref "R50") (pin "2") (pintype "passive"))
      (node (ref "R51") (pin "1") (pintype "passive"))
    )
    (net (code "221") (name "Net-(K17-Pad3)") (class "Default")
      (node (ref "K17") (pin "3") (pinfunction "3_3") (pintype "passive"))
      (node (ref "R53") (pin "1") (pintype "passive"))
      (node (ref "R63") (pin "1") (pintype "passive"))
    )
    (net (code "222") (name "Net-(K17-Pad6)") (class "Default")
      (node (ref "K17") (pin "6") (pinfunction "6_6") (pintype "passive"))
      (node (ref "R54") (pin "1") (pintype "passive"))
      (node (ref "R70") (pin "1") (pintype "passive"))
    )
    (net (code "223") (name "Net-(K18-Pad3)") (class "Default")
      (node (ref "K18") (pin "3") (pinfunction "3_3") (pintype "passive"))
      (node (ref "R55") (pin "1") (pintype "passive"))
      (node (ref "R63") (pin "2") (pintype "passive"))
      (node (ref "R64") (pin "1") (pintype "passive"))
    )
    (net (code "224") (name "Net-(K18-Pad6)") (class "Default")
      (node (ref "K18") (pin "6") (pinfunction "6_6") (pintype "passive"))
      (node (ref "R56") (pin "1") (pintype "passive"))
      (node (ref "R70") (pin "2") (pintype "passive"))
      (node (ref "R71") (pin "1") (pintype "passive"))
    )
    (net (code "225") (name "Net-(K19-Pad3)") (class "Default")
      (node (ref "K19") (pin "3") (pinfunction "3_3") (pintype "passive"))
      (node (ref "R57") (pin "1") (pintype "passive"))
      (node (ref "R64") (pin "2") (pintype "passive"))
      (node (ref "R65") (pin "1") (pintype "passive"))
    )
    (net (code "226") (name "Net-(K19-Pad6)") (class "Default")
      (node (ref "K19") (pin "6") (pinfunction "6_6") (pintype "passive"))
      (node (ref "R58") (pin "1") (pintype "passive"))
      (node (ref "R71") (pin "2") (pintype "passive"))
      (node (ref "R72") (pin "1") (pintype "passive"))
    )
    (net (code "227") (name "Net-(K20-Pad3)") (class "Default")
      (node (ref "K20") (pin "3") (pinfunction "3_3") (pintype "passive"))
      (node (ref "R59") (pin "1") (pintype "passive"))
      (node (ref "R65") (pin "2") (pintype "passive"))
      (node (ref "R66") (pin "1") (pintype "passive"))
    )
    (net (code "228") (name "Net-(K20-Pad6)") (class "Default")
      (node (ref "K20") (pin "6") (pinfunction "6_6") (pintype "passive"))
      (node (ref "R60") (pin "1") (pintype "passive"))
      (node (ref "R72") (pin "2") (pintype "passive"))
      (node (ref "R73") (pin "1") (pintype "passive"))
    )
    (net (code "229") (name "Net-(K21-Pad3)") (class "Default")
      (node (ref "K21") (pin "3") (pinfunction "3_3") (pintype "passive"))
      (node (ref "R66") (pin "2") (pintype "passive"))
      (node (ref "R67") (pin "1") (pintype "passive"))
    )
    (net (code "230") (name "Net-(K21-Pad6)") (class "Default")
      (node (ref "K21") (pin "6") (pinfunction "6_6") (pintype "passive"))
      (node (ref "R73") (pin "2") (pintype "passive"))
      (node (ref "R74") (pin "1") (pintype "passive"))
    )
    (net (code "231") (name "Net-(K22-Pad3)") (class "Default")
      (node (ref "K22") (pin "3") (pinfunction "3_3") (pintype "passive"))
      (node (ref "R67") (pin "2") (pintype "passive"))
      (node (ref "R68") (pin "1") (pintype "passive"))
    )
    (net (code "232") (name "Net-(K22-Pad6)") (class "Default")
      (node (ref "K22") (pin "6") (pinfunction "6_6") (pintype "passive"))
      (node (ref "R74") (pin "2") (pintype "passive"))
      (node (ref "R75") (pin "1") (pintype "passive"))
    )
    (net (code "233") (name "Net-(K23-Pad3)") (class "Default")
      (node (ref "K23") (pin "3") (pinfunction "3_3") (pintype "passive"))
      (node (ref "R68") (pin "2") (pintype "passive"))
      (node (ref "R69") (pin "1") (pintype "passive"))
    )
    (net (code "234") (name "Net-(K23-Pad6)") (class "Default")
      (node (ref "K23") (pin "6") (pinfunction "6_6") (pintype "passive"))
      (node (ref "R75") (pin "2") (pintype "passive"))
      (node (ref "R76") (pin "1") (pintype "passive"))
    )
    (net (code "235") (name "Net-(MCP1-GPA0)") (class "Default")
      (node (ref "MCP1") (pin "17") (pinfunction "GPA0_17") (pintype "passive"))
      (node (ref "ULN2") (pin "6") (pinfunction "B8_6") (pintype "passive"))
    )
    (net (code "236") (name "Net-(MCP1-GPA1)") (class "Default")
      (node (ref "MCP1") (pin "18") (pinfunction "GPA1_18") (pintype "passive"))
      (node (ref "ULN2") (pin "5") (pinfunction "B7_5") (pintype "passive"))
    )
    (net (code "237") (name "Net-(MCP1-GPA2)") (class "Default")
      (node (ref "MCP1") (pin "19") (pinfunction "GPA2_19") (pintype "passive"))
      (node (ref "ULN2") (pin "4") (pinfunction "B6_4") (pintype "passive"))
    )
    (net (code "238") (name "Net-(MCP1-GPA3)") (class "Default")
      (node (ref "MCP1") (pin "20") (pinfunction "GPA3_20") (pintype "passive"))
      (node (ref "ULN2") (pin "3") (pinfunction "B5_3") (pintype "passive"))
    )
    (net (code "239") (name "Net-(MCP1-GPA4)") (class "Default")
      (node (ref "MCP1") (pin "21") (pinfunction "GPA4_21") (pintype "passive"))
      (node (ref "ULN2") (pin "2") (pinfunction "B4_2") (pintype "passive"))
    )
    (net (code "240") (name "Net-(MCP1-GPA5)") (class "Default")
      (node (ref "MCP1") (pin "22") (pinfunction "GPA5_22") (pintype "passive"))
      (node (ref "ULN2") (pin "1") (pinfunction "B3_1") (pintype "passive"))
    )
    (net (code "241") (name "Net-(MCP1-GPA6)") (class "Default")
      (node (ref "MCP1") (pin "23") (pinfunction "GPA6_23") (pintype "passive"))
      (node (ref "ULN2") (pin "20") (pinfunction "B2_20") (pintype "passive"))
    )
    (net (code "242") (name "Net-(MCP1-GPA7)") (class "Default")
      (node (ref "MCP1") (pin "24") (pinfunction "GPA7_24") (pintype "passive"))
      (node (ref "ULN2") (pin "19") (pinfunction "B1_19") (pintype "passive"))
    )
    (net (code "243") (name "Net-(MCP1-GPB0)") (class "Default")
      (node (ref "MCP1") (pin "25") (pinfunction "GPB0_25") (pintype "passive"))
      (node (ref "ULN1") (pin "6") (pinfunction "B8_6") (pintype "passive"))
    )
    (net (code "244") (name "Net-(MCP1-GPB1)") (class "Default")
      (node (ref "MCP1") (pin "26") (pinfunction "GPB1_26") (pintype "passive"))
      (node (ref "ULN1") (pin "5") (pinfunction "B7_5") (pintype "passive"))
    )
    (net (code "245") (name "Net-(MCP1-GPB2)") (class "Default")
      (node (ref "MCP1") (pin "27") (pinfunction "GPB2_27") (pintype "passive"))
      (node (ref "ULN1") (pin "4") (pinfunction "B6_4") (pintype "passive"))
    )
    (net (code "246") (name "Net-(MCP1-GPB3)") (class "Default")
      (node (ref "MCP1") (pin "28") (pinfunction "GPB3_28") (pintype "passive"))
      (node (ref "ULN1") (pin "3") (pinfunction "B5_3") (pintype "passive"))
    )
    (net (code "247") (name "Net-(MCP1-GPB4)") (class "Default")
      (node (ref "MCP1") (pin "1") (pinfunction "GPB4_1") (pintype "passive"))
      (node (ref "ULN1") (pin "2") (pinfunction "B4_2") (pintype "passive"))
    )
    (net (code "248") (name "Net-(MCP1-GPB5)") (class "Default")
      (node (ref "MCP1") (pin "2") (pinfunction "GPB5_2") (pintype "passive"))
      (node (ref "ULN1") (pin "1") (pinfunction "B3_1") (pintype "passive"))
    )
    (net (code "249") (name "Net-(MCP1-GPB6)") (class "Default")
      (node (ref "MCP1") (pin "3") (pinfunction "GPB6_3") (pintype "passive"))
      (node (ref "ULN1") (pin "20") (pinfunction "B2_20") (pintype "passive"))
    )
    (net (code "250") (name "Net-(MCP1-GPB7)") (class "Default")
      (node (ref "MCP1") (pin "4") (pinfunction "GPB7_4") (pintype "passive"))
      (node (ref "ULN1") (pin "19") (pinfunction "B1_19") (pintype "passive"))
    )
    (net (code "251") (name "Net-(MCP1-~{RESET})") (class "Default")
      (node (ref "C2") (pin "2") (pinfunction "2_2") (pintype "passive"))
      (node (ref "MCP1") (pin "14") (pinfunction "~{RESET}_14") (pintype "passive"))
      (node (ref "R37") (pin "2") (pintype "passive"))
    )
    (net (code "252") (name "Net-(MCP2-GPA0)") (class "Default")
      (node (ref "MCP2") (pin "17") (pinfunction "GPA0_17") (pintype "passive"))
      (node (ref "ULN3") (pin "6") (pinfunction "B8_6") (pintype "passive"))
    )
    (net (code "253") (name "Net-(MCP2-GPA1)") (class "Default")
      (node (ref "MCP2") (pin "18") (pinfunction "GPA1_18") (pintype "passive"))
      (node (ref "ULN3") (pin "5") (pinfunction "B7_5") (pintype "passive"))
    )
    (net (code "254") (name "Net-(MCP2-GPA2)") (class "Default")
      (node (ref "MCP2") (pin "19") (pinfunction "GPA2_19") (pintype "passive"))
      (node (ref "ULN3") (pin "4") (pinfunction "B6_4") (pintype "passive"))
    )
    (net (code "255") (name "Net-(MCP2-GPA3)") (class "Default")
      (node (ref "MCP2") (pin "20") (pinfunction "GPA3_20") (pintype "passive"))
      (node (ref "ULN3") (pin "3") (pinfunction "B5_3") (pintype "passive"))
    )
    (net (code "256") (name "Net-(MCP2-GPA4)") (class "Default")
      (node (ref "MCP2") (pin "21") (pinfunction "GPA4_21") (pintype "passive"))
      (node (ref "ULN3") (pin "2") (pinfunction "B4_2") (pintype "passive"))
    )
    (net (code "257") (name "Net-(MCP2-GPA5)") (class "Default")
      (node (ref "MCP2") (pin "22") (pinfunction "GPA5_22") (pintype "passive"))
      (node (ref "ULN3") (pin "1") (pinfunction "B3_1") (pintype "passive"))
    )
    (net (code "258") (name "Net-(MCP2-GPA6)") (class "Default")
      (node (ref "MCP2") (pin "23") (pinfunction "GPA6_23") (pintype "passive"))
      (node (ref "ULN3") (pin "20") (pinfunction "B2_20") (pintype "passive"))
    )
    (net (code "259") (name "Net-(MCP2-GPA7)") (class "Default")
      (node (ref "MCP2") (pin "24") (pinfunction "GPA7_24") (pintype "passive"))
      (node (ref "ULN3") (pin "19") (pinfunction "B1_19") (pintype "passive"))
    )
    (net (code "260") (name "Net-(MCP2-GPB0)") (class "Default")
      (node (ref "MCP2") (pin "25") (pinfunction "GPB0_25") (pintype "passive"))
      (node (ref "ULN4") (pin "6") (pinfunction "B8_6") (pintype "passive"))
    )
    (net (code "261") (name "Net-(MCP2-GPB1)") (class "Default")
      (node (ref "MCP2") (pin "26") (pinfunction "GPB1_26") (pintype "passive"))
      (node (ref "ULN4") (pin "5") (pinfunction "B7_5") (pintype "passive"))
    )
    (net (code "262") (name "Net-(MCP2-GPB2)") (class "Default")
      (node (ref "MCP2") (pin "27") (pinfunction "GPB2_27") (pintype "passive"))
      (node (ref "ULN4") (pin "4") (pinfunction "B6_4") (pintype "passive"))
    )
    (net (code "263") (name "Net-(MCP2-GPB3)") (class "Default")
      (node (ref "MCP2") (pin "28") (pinfunction "GPB3_28") (pintype "passive"))
      (node (ref "ULN4") (pin "3") (pinfunction "B5_3") (pintype "passive"))
    )
    (net (code "264") (name "Net-(MCP2-GPB4)") (class "Default")
      (node (ref "MCP2") (pin "1") (pinfunction "GPB4_1") (pintype "passive"))
      (node (ref "ULN4") (pin "2") (pinfunction "B4_2") (pintype "passive"))
    )
    (net (code "265") (name "Net-(MCP2-GPB5)") (class "Default")
      (node (ref "MCP2") (pin "2") (pinfunction "GPB5_2") (pintype "passive"))
      (node (ref "ULN4") (pin "1") (pinfunction "B3_1") (pintype "passive"))
    )
    (net (code "266") (name "Net-(MCP2-GPB6)") (class "Default")
      (node (ref "MCP2") (pin "3") (pinfunction "GPB6_3") (pintype "passive"))
      (node (ref "ULN4") (pin "20") (pinfunction "B2_20") (pintype "passive"))
    )
    (net (code "267") (name "Net-(MCP2-GPB7)") (class "Default")
      (node (ref "MCP2") (pin "4") (pinfunction "GPB7_4") (pintype "passive"))
      (node (ref "ULN4") (pin "19") (pinfunction "B1_19") (pintype "passive"))
    )
    (net (code "268") (name "Net-(MCP2-~{RESET})") (class "Default")
      (node (ref "C6") (pin "2") (pinfunction "2_2") (pintype "passive"))
      (node (ref "MCP2") (pin "14") (pinfunction "~{RESET}_14") (pintype "passive"))
      (node (ref "R52") (pin "2") (pintype "passive"))
    )
    (net (code "269") (name "Net-(U1-PB2_(~{SS}{slash}OC1B{slash}PCINT2))") (class "Default")
      (node (ref "R77") (pin "2") (pintype "passive"))
      (node (ref "U1") (pin "12") (pinfunction "PB2_(~{SS}/OC1B/PCINT2)_12") (pintype "bidirectional"))
    )
    (net (code "270") (name "Net-(U1-PB3_(MOSI{slash}PCINT3))") (class "Default")
      (node (ref "R78") (pin "2") (pintype "passive"))
      (node (ref "U1") (pin "13") (pinfunction "PB3_(MOSI/PCINT3)_13") (pintype "bidirectional"))
    )
    (net (code "271") (name "Net-(U1-PB5_(SCK{slash}PCINT5))") (class "Default")
      (node (ref "R79") (pin "2") (pintype "passive"))
      (node (ref "U1") (pin "15") (pinfunction "PB5_(SCK/PCINT5)_15") (pintype "bidirectional"))
    )
    (net (code "272") (name "Net-(U1-PB7_(PCINT7))") (class "Default")
      (node (ref "R80") (pin "2") (pintype "passive"))
      (node (ref "U1") (pin "6") (pinfunction "PB7_(PCINT7)_6") (pintype "bidirectional"))
    )
    (net (code "273") (name "unconnected-(K5-Pad2)") (class "Default")
      (node (ref "K5") (pin "2") (pinfunction "2_2") (pintype "passive+no_connect"))
    )
    (net (code "274") (name "unconnected-(K5-Pad7)") (class "Default")
      (node (ref "K5") (pin "7") (pinfunction "7_7") (pintype "passive+no_connect"))
    )
    (net (code "275") (name "unconnected-(K6-Pad2)") (class "Default")
      (node (ref "K6") (pin "2") (pinfunction "2_2") (pintype "passive+no_connect"))
    )
    (net (code "276") (name "unconnected-(K6-Pad7)") (class "Default")
      (node (ref "K6") (pin "7") (pinfunction "7_7") (pintype "passive+no_connect"))
    )
    (net (code "277") (name "unconnected-(K7-Pad2)") (class "Default")
      (node (ref "K7") (pin "2") (pinfunction "2_2") (pintype "passive+no_connect"))
    )
    (net (code "278") (name "unconnected-(K7-Pad7)") (class "Default")
      (node (ref "K7") (pin "7") (pinfunction "7_7") (pintype "passive+no_connect"))
    )
    (net (code "279") (name "unconnected-(K8-Pad2)") (class "Default")
      (node (ref "K8") (pin "2") (pinfunction "2_2") (pintype "passive+no_connect"))
    )
    (net (code "280") (name "unconnected-(K8-Pad7)") (class "Default")
      (node (ref "K8") (pin "7") (pinfunction "7_7") (pintype "passive+no_connect"))
    )
    (net (code "281") (name "unconnected-(K13-Pad2)") (class "Default")
      (node (ref "K13") (pin "2") (pinfunction "2_2") (pintype "passive+no_connect"))
    )
    (net (code "282") (name "unconnected-(K13-Pad7)") (class "Default")
      (node (ref "K13") (pin "7") (pinfunction "7_7") (pintype "passive+no_connect"))
    )
    (net (code "283") (name "unconnected-(K14-Pad2)") (class "Default")
      (node (ref "K14") (pin "2") (pinfunction "2_2") (pintype "passive+no_connect"))
    )
    (net (code "284") (name "unconnected-(K14-Pad7)") (class "Default")
      (node (ref "K14") (pin "7") (pinfunction "7_7") (pintype "passive+no_connect"))
    )
    (net (code "285") (name "unconnected-(K15-Pad2)") (class "Default")
      (node (ref "K15") (pin "2") (pinfunction "2_2") (pintype "passive+no_connect"))
    )
    (net (code "286") (name "unconnected-(K15-Pad7)") (class "Default")
      (node (ref "K15") (pin "7") (pinfunction "7_7") (pintype "passive+no_connect"))
    )
    (net (code "287") (name "unconnected-(K16-Pad2)") (class "Default")
      (node (ref "K16") (pin "2") (pinfunction "2_2") (pintype "passive+no_connect"))
    )
    (net (code "288") (name "unconnected-(K16-Pad7)") (class "Default")
      (node (ref "K16") (pin "7") (pinfunction "7_7") (pintype "passive+no_connect"))
    )
    (net (code "289") (name "unconnected-(K21-Pad2)") (class "Default")
      (node (ref "K21") (pin "2") (pinfunction "2_2") (pintype "passive+no_connect"))
    )
    (net (code "290") (name "unconnected-(K21-Pad7)") (class "Default")
      (node (ref "K21") (pin "7") (pinfunction "7_7") (pintype "passive+no_connect"))
    )
    (net (code "291") (name "unconnected-(K22-Pad2)") (class "Default")
      (node (ref "K22") (pin "2") (pinfunction "2_2") (pintype "passive+no_connect"))
    )
    (net (code "292") (name "unconnected-(K22-Pad7)") (class "Default")
      (node (ref "K22") (pin "7") (pinfunction "7_7") (pintype "passive+no_connect"))
    )
    (net (code "293") (name "unconnected-(K23-Pad2)") (class "Default")
      (node (ref "K23") (pin "2") (pinfunction "2_2") (pintype "passive+no_connect"))
    )
    (net (code "294") (name "unconnected-(K23-Pad7)") (class "Default")
      (node (ref "K23") (pin "7") (pinfunction "7_7") (pintype "passive+no_connect"))
    )
    (net (code "295") (name "unconnected-(K24-Pad2)") (class "Default")
      (node (ref "K24") (pin "2") (pinfunction "2_2") (pintype "passive+no_connect"))
    )
    (net (code "296") (name "unconnected-(K24-Pad7)") (class "Default")
      (node (ref "K24") (pin "7") (pinfunction "7_7") (pintype "passive+no_connect"))
    )
    (net (code "297") (name "unconnected-(LD1-N{slash}C-Pad4)") (class "Default")
      (node (ref "LD1") (pin "4") (pinfunction "N/C_4") (pintype "passive+no_connect"))
    )
    (net (code "298") (name "unconnected-(MCP1-INTA-Pad16)") (class "Default")
      (node (ref "MCP1") (pin "16") (pinfunction "INTA_16") (pintype "passive+no_connect"))
    )
    (net (code "299") (name "unconnected-(MCP1-INTB-Pad15)") (class "Default")
      (node (ref "MCP1") (pin "15") (pinfunction "INTB_15") (pintype "passive+no_connect"))
    )
    (net (code "300") (name "unconnected-(MCP2-INTA-Pad16)") (class "Default")
      (node (ref "MCP2") (pin "16") (pinfunction "INTA_16") (pintype "passive+no_connect"))
    )
    (net (code "301") (name "unconnected-(MCP2-INTB-Pad15)") (class "Default")
      (node (ref "MCP2") (pin "15") (pinfunction "INTB_15") (pintype "passive+no_connect"))
    )
    (net (code "302") (name "unconnected-(U1-PB0_(PCINT0{slash}CLKO{slash}ICP1)-Pad10)") (class "Default")
      (node (ref "U1") (pin "10") (pinfunction "PB0_(PCINT0/CLKO/ICP1)_10") (pintype "bidirectional"))
    )
    (net (code "303") (name "unconnected-(U1-PB1_(OC1A{slash}PCINT1)-Pad11)") (class "Default")
      (node (ref "U1") (pin "11") (pinfunction "PB1_(OC1A/PCINT1)_11") (pintype "bidirectional"))
    )
    (net (code "304") (name "unconnected-(U1-PB6_(PCINT6{slash}CLKI)-Pad5)") (class "Default")
      (node (ref "U1") (pin "5") (pinfunction "PB6_(PCINT6/CLKI)_5") (pintype "bidirectional"))
    )
    (net (code "305") (name "unconnected-(U1-PC0_(ADC0{slash}PCINT8)-Pad19)") (class "Default")
      (node (ref "U1") (pin "19") (pinfunction "PC0_(ADC0/PCINT8)_19") (pintype "bidirectional"))
    )
    (net (code "306") (name "unconnected-(U1-PC1_(ADC1{slash}PCINT9)-Pad20)") (class "Default")
      (node (ref "U1") (pin "20") (pinfunction "PC1_(ADC1/PCINT9)_20") (pintype "bidirectional"))
    )
    (net (code "307") (name "unconnected-(U1-PC2_(ADC2{slash}PCINT10)-Pad21)") (class "Default")
      (node (ref "U1") (pin "21") (pinfunction "PC2_(ADC2/PCINT10)_21") (pintype "bidirectional"))
    )
    (net (code "308") (name "unconnected-(U1-PC3_(ADC3{slash}PCINT11)-Pad22)") (class "Default")
      (node (ref "U1") (pin "22") (pinfunction "PC3_(ADC3/PCINT11)_22") (pintype "bidirectional"))
    )
    (net (code "309") (name "unconnected-(U1-PC7_(PCINT15)-Pad17)") (class "Default")
      (node (ref "U1") (pin "17") (pinfunction "PC7_(PCINT15)_17") (pintype "bidirectional"))
    )
    (net (code "310") (name "unconnected-(U1-PD0_(PCINT16)-Pad26)") (class "Default")
      (node (ref "U1") (pin "26") (pinfunction "PD0_(PCINT16)_26") (pintype "bidirectional"))
    )
    (net (code "311") (name "unconnected-(U1-PD1_(PCINT17)-Pad27)") (class "Default")
      (node (ref "U1") (pin "27") (pinfunction "PD1_(PCINT17)_27") (pintype "bidirectional"))
    )
    (net (code "312") (name "unconnected-(U1-PD2_(PCINT18{slash}INT0)-Pad28)") (class "Default")
      (node (ref "U1") (pin "28") (pinfunction "PD2_(PCINT18/INT0)_28") (pintype "bidirectional"))
    )
    (net (code "313") (name "unconnected-(U1-PD3_(PCINT19{slash}INT1)-Pad1)") (class "Default")
      (node (ref "U1") (pin "1") (pinfunction "PD3_(PCINT19/INT1)_1") (pintype "bidirectional"))
    )
    (net (code "314") (name "unconnected-(U1-PD4_(PCINT20{slash}T0)-Pad2)") (class "Default")
      (node (ref "U1") (pin "2") (pinfunction "PD4_(PCINT20/T0)_2") (pintype "bidirectional"))
    )
    (net (code "315") (name "unconnected-(U1-PD5_(PCINT21{slash}T1)-Pad7)") (class "Default")
      (node (ref "U1") (pin "7") (pinfunction "PD5_(PCINT21/T1)_7") (pintype "bidirectional"))
    )
    (net (code "316") (name "unconnected-(U1-PD6_(PCINT22{slash}AIN0)-Pad8)") (class "Default")
      (node (ref "U1") (pin "8") (pinfunction "PD6_(PCINT22/AIN0)_8") (pintype "bidirectional"))
    )
    (net (code "317") (name "unconnected-(U1-PD7_(PCINT23{slash}AIN1)-Pad9)") (class "Default")
      (node (ref "U1") (pin "9") (pinfunction "PD7_(PCINT23/AIN1)_9") (pintype "bidirectional"))
    )
    (net (code "318") (name "unconnected-(ULN4-C7-Pad11)") (class "Default")
      (node (ref "ULN4") (pin "11") (pinfunction "C7_11") (pintype "passive"))
    )
    (net (code "319") (name "unconnected-(ULN4-C8-Pad10)") (class "Default")
      (node (ref "ULN4") (pin "10") (pinfunction "C8_10") (pintype "passive"))
    )
  )
)
